# FPGA.net
KiCad netlist of a schematic drawn in Altium Designer
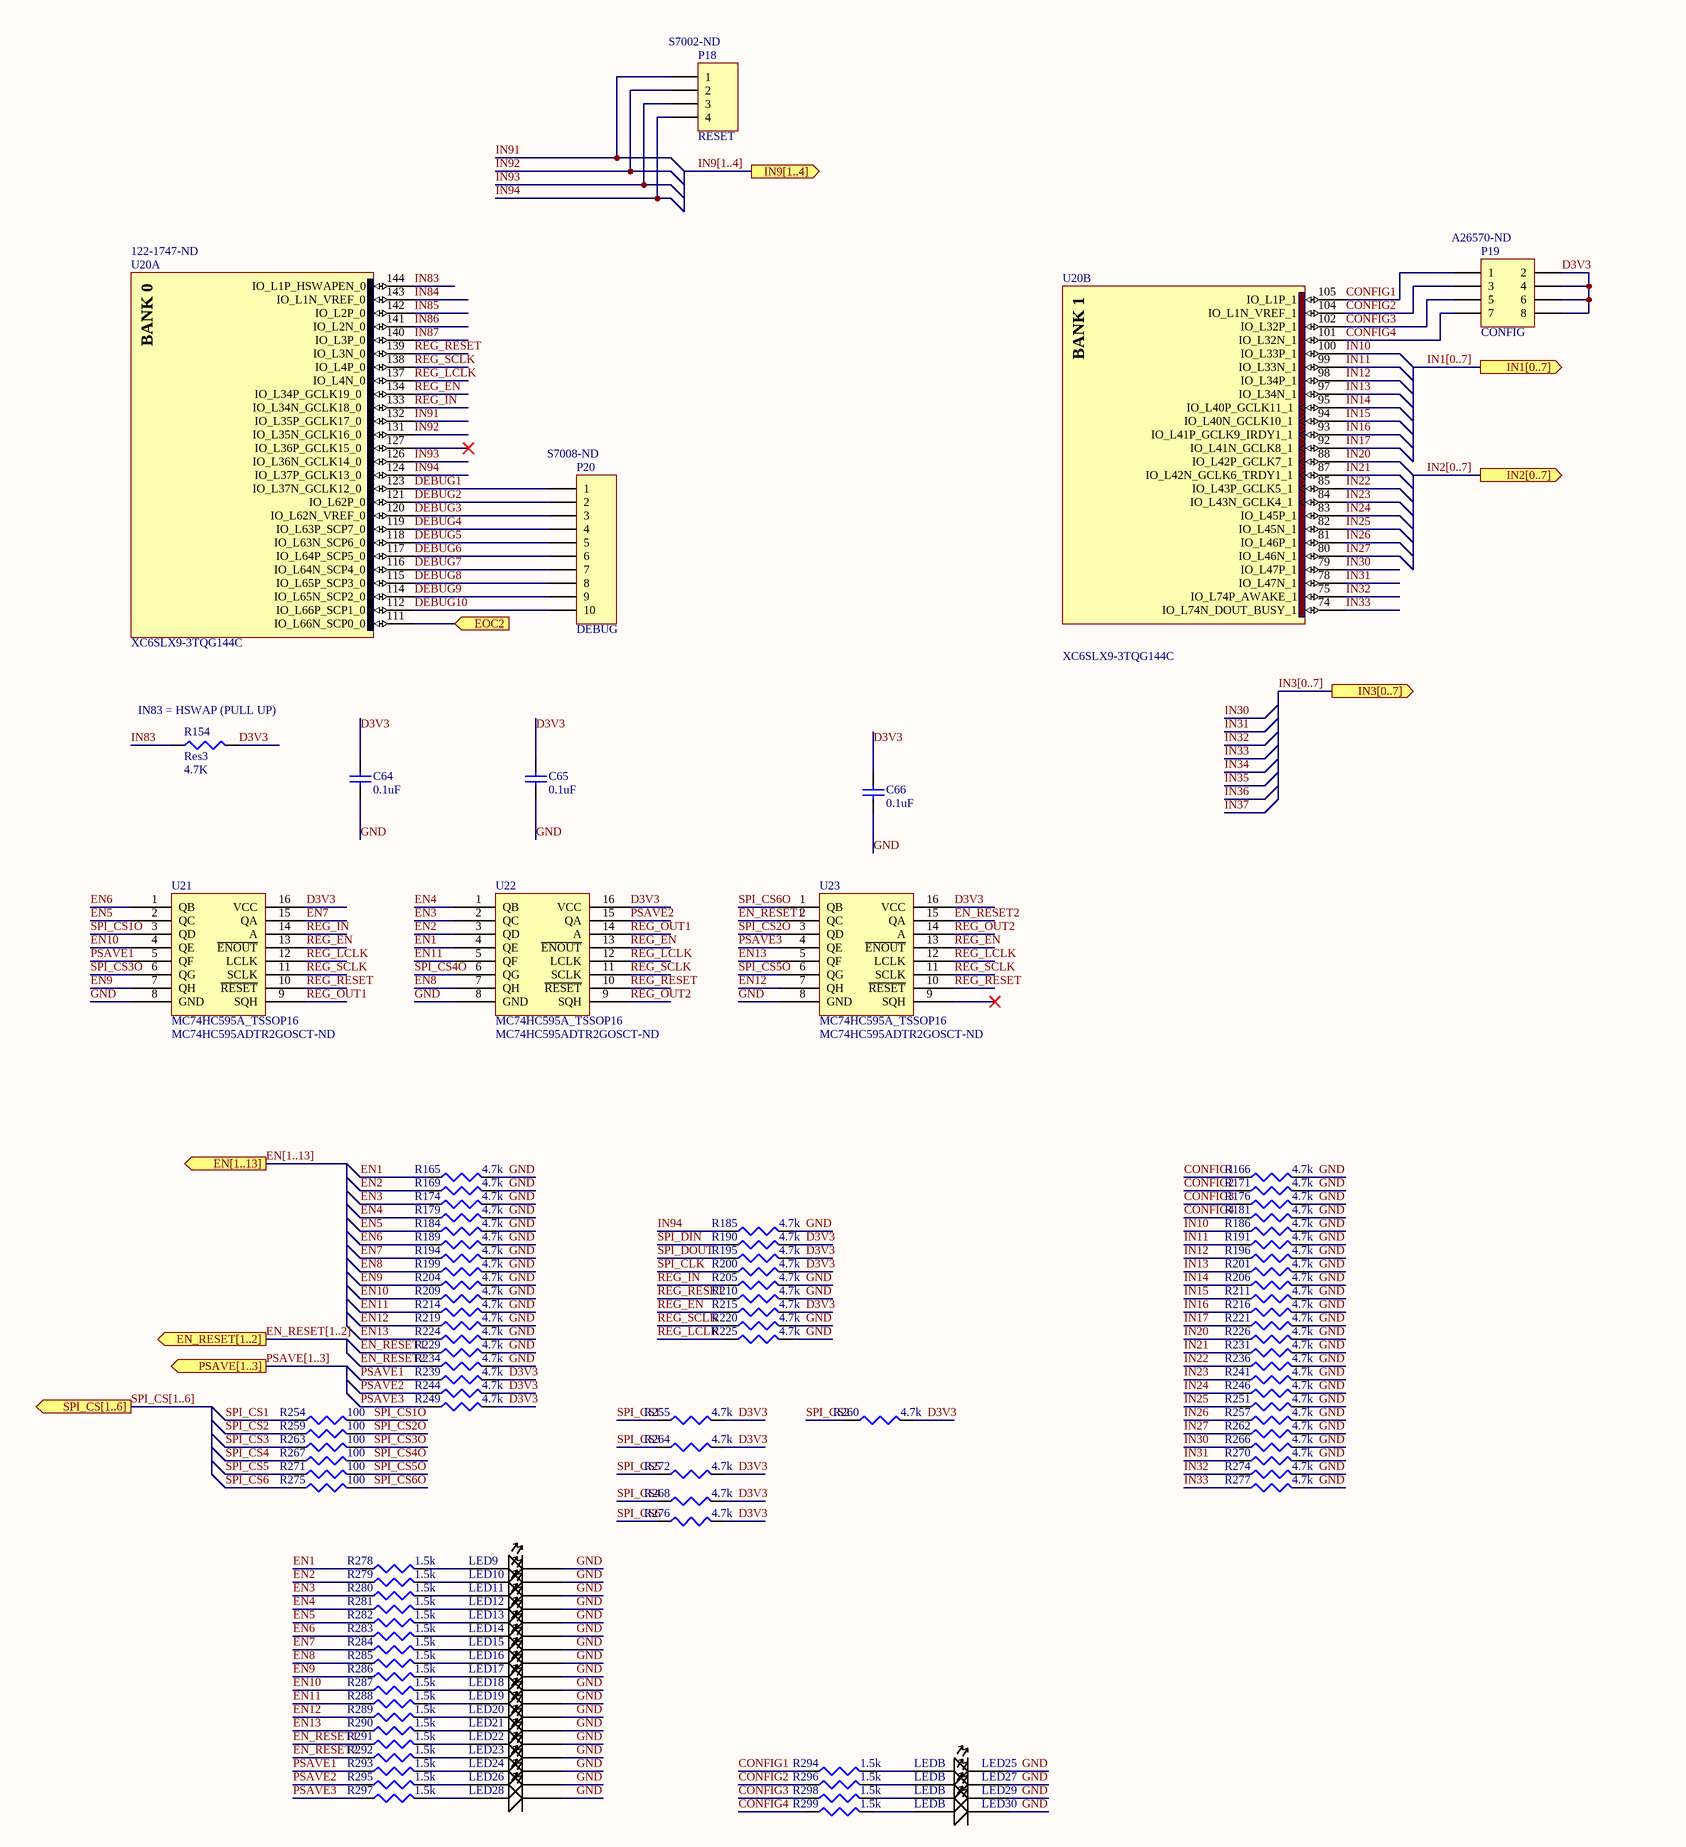
[diagram p0: FPGA.SchDoc, top left]
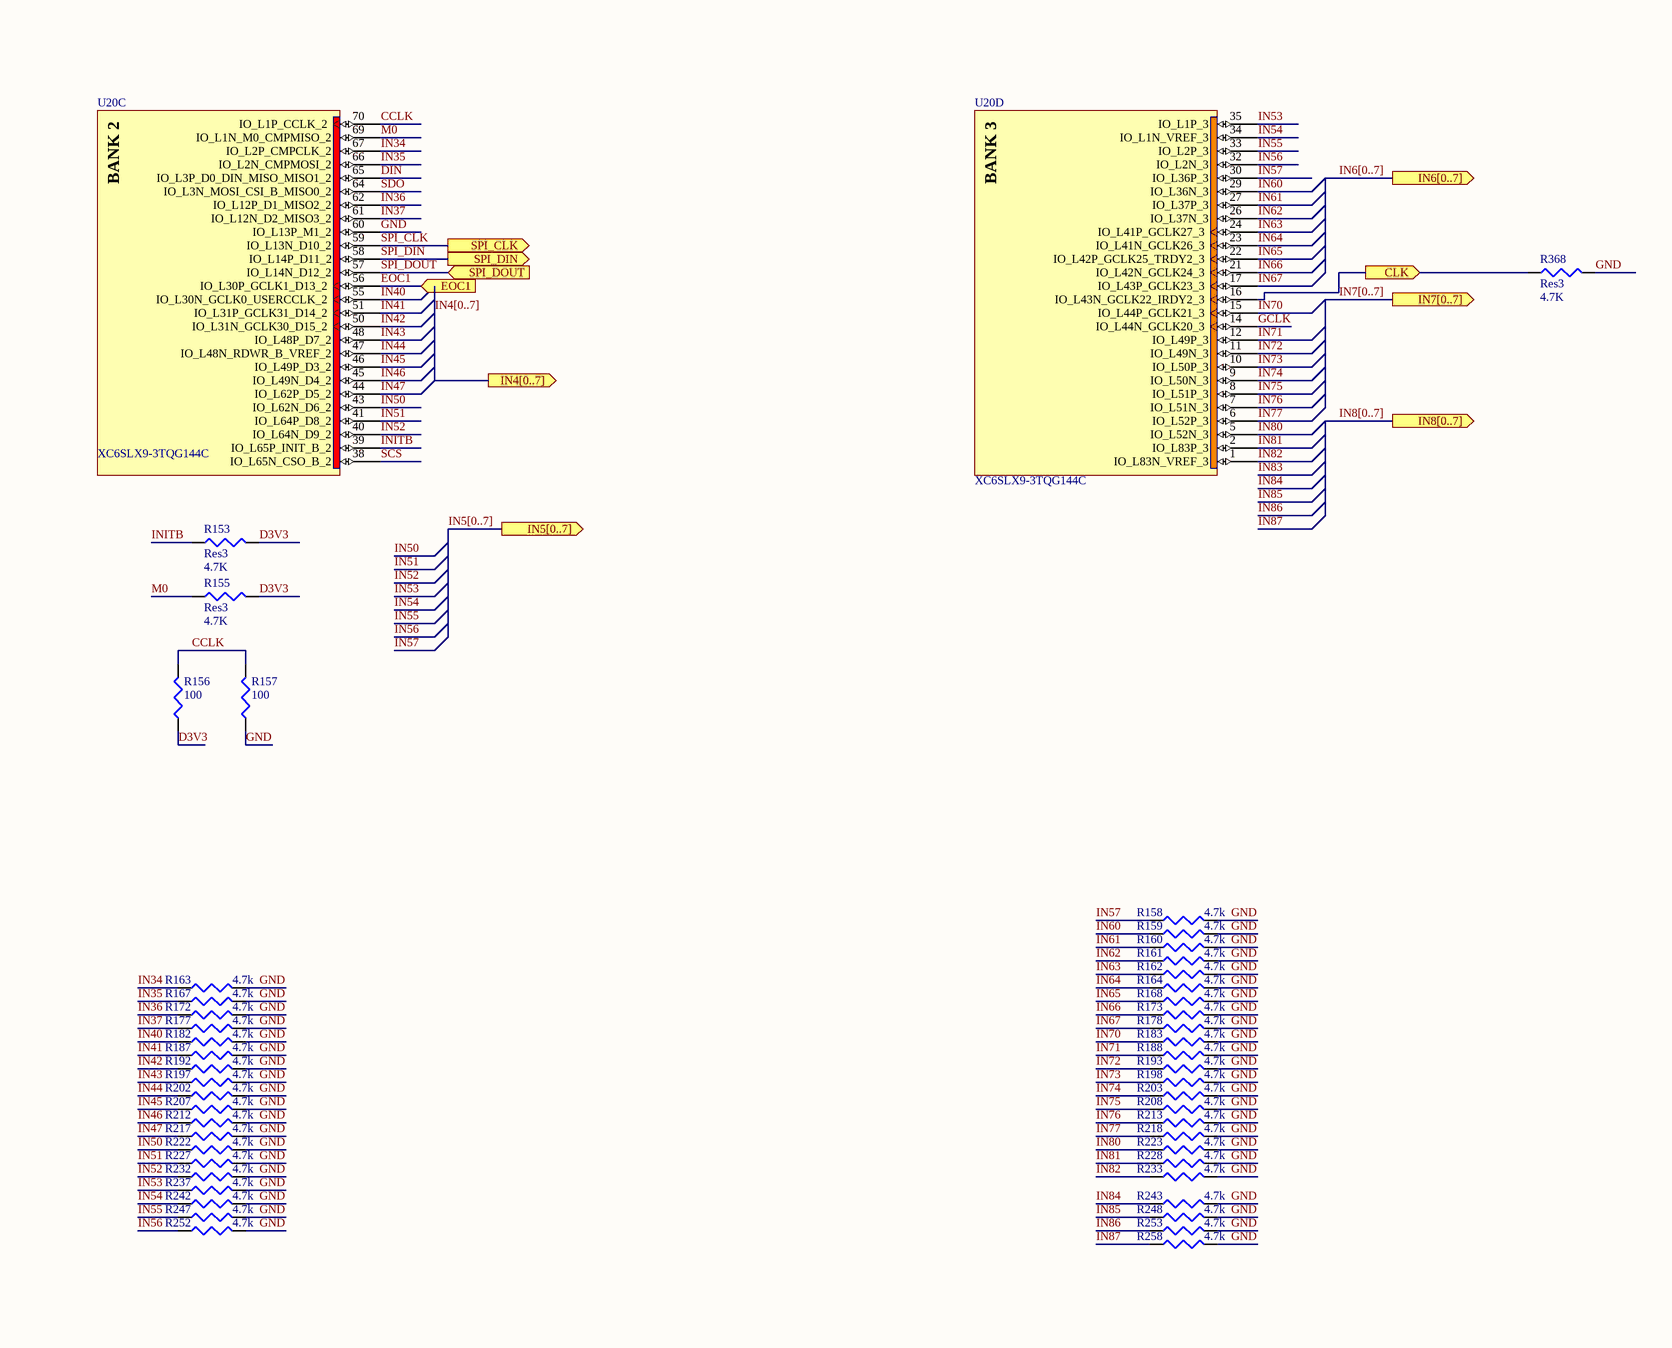
[diagram p1: FPGA.SchDoc, top right]
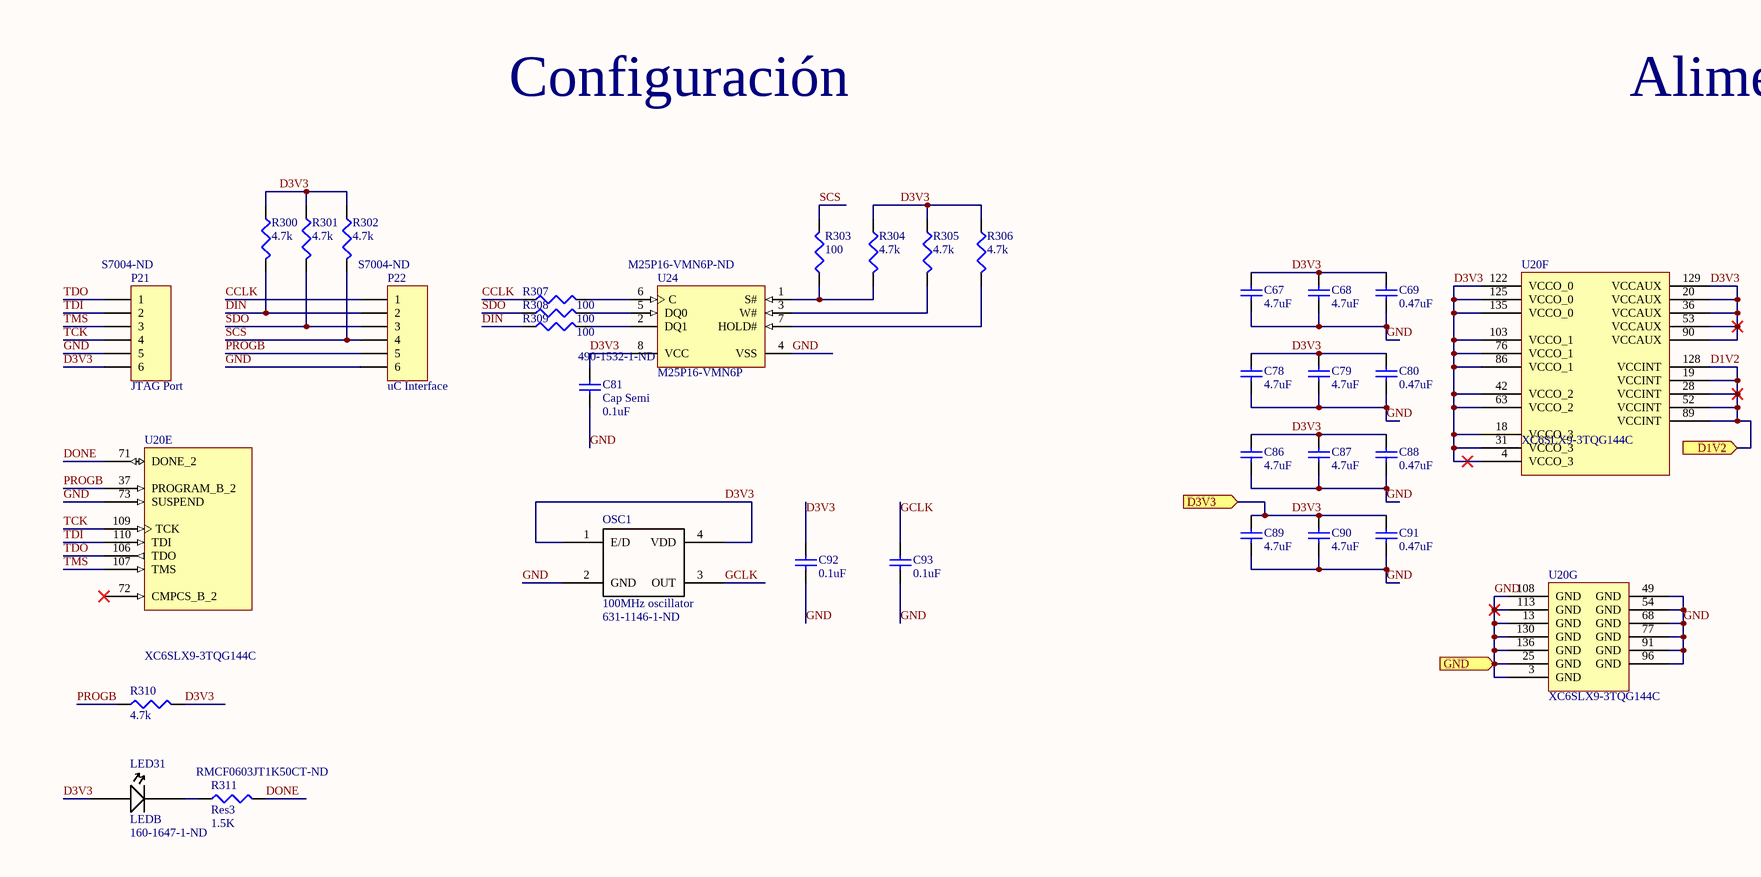
[diagram p2: FPGA.SchDoc, bottom left]
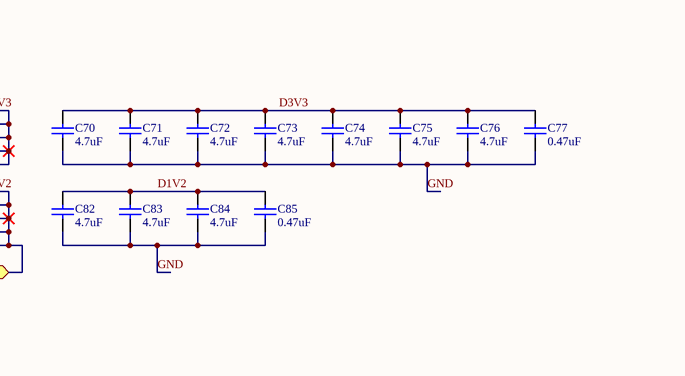
[diagram p3: FPGA.SchDoc, bottom right]

(export (version "E")
  (design (tool "Eeschema 10.0.6"))
  (components
    (comp (ref "C64")
      (value "0.1uF")
      (footprint "J1-0603")
      (description "Capacitor")
      (fields (field (name "Comment") "Cap") (field (name "PUBLISHER") "Altium Limited"))
      (libsource (lib "Miscellaneous Devices") (part "Cap"))
    )
    (comp (ref "C65")
      (value "0.1uF")
      (footprint "J1-0603")
      (description "Capacitor")
      (fields (field (name "Comment") "Cap") (field (name "PUBLISHER") "Altium Limited"))
      (libsource (lib "Miscellaneous Devices") (part "Cap"))
    )
    (comp (ref "C66")
      (value "0.1uF")
      (footprint "J1-0603")
      (description "Capacitor")
      (fields (field (name "Comment") "Cap") (field (name "PUBLISHER") "Altium Limited"))
      (libsource (lib "Miscellaneous Devices") (part "Cap"))
    )
    (comp (ref "C67")
      (value "4.7uF")
      (footprint "J1-0603")
      (description "Capacitor")
      (fields (field (name "Comment") "Cap") (field (name "PUBLISHER") "Altium Limited"))
      (libsource (lib "Miscellaneous Devices") (part "Cap"))
    )
    (comp (ref "C68")
      (value "4.7uF")
      (footprint "J1-0603")
      (description "Capacitor")
      (fields (field (name "Comment") "Cap") (field (name "PUBLISHER") "Altium Limited"))
      (libsource (lib "Miscellaneous Devices") (part "Cap"))
    )
    (comp (ref "C69")
      (value "0.47uF")
      (footprint "J1-0603")
      (description "Capacitor")
      (fields (field (name "Comment") "Cap") (field (name "PUBLISHER") "Altium Limited"))
      (libsource (lib "Miscellaneous Devices") (part "Cap"))
    )
    (comp (ref "C70")
      (value "4.7uF")
      (footprint "J1-0603")
      (description "Capacitor")
      (fields (field (name "Comment") "Cap") (field (name "PUBLISHER") "Altium Limited"))
      (libsource (lib "Miscellaneous Devices") (part "Cap"))
    )
    (comp (ref "C71")
      (value "4.7uF")
      (footprint "J1-0603")
      (description "Capacitor")
      (fields (field (name "Comment") "Cap") (field (name "PUBLISHER") "Altium Limited"))
      (libsource (lib "Miscellaneous Devices") (part "Cap"))
    )
    (comp (ref "C72")
      (value "4.7uF")
      (footprint "J1-0603")
      (description "Capacitor")
      (fields (field (name "Comment") "Cap") (field (name "PUBLISHER") "Altium Limited"))
      (libsource (lib "Miscellaneous Devices") (part "Cap"))
    )
    (comp (ref "C73")
      (value "4.7uF")
      (footprint "J1-0603")
      (description "Capacitor")
      (fields (field (name "Comment") "Cap") (field (name "PUBLISHER") "Altium Limited"))
      (libsource (lib "Miscellaneous Devices") (part "Cap"))
    )
    (comp (ref "C74")
      (value "4.7uF")
      (footprint "J1-0603")
      (description "Capacitor")
      (fields (field (name "Comment") "Cap") (field (name "PUBLISHER") "Altium Limited"))
      (libsource (lib "Miscellaneous Devices") (part "Cap"))
    )
    (comp (ref "C75")
      (value "4.7uF")
      (footprint "J1-0603")
      (description "Capacitor")
      (fields (field (name "Comment") "Cap") (field (name "PUBLISHER") "Altium Limited"))
      (libsource (lib "Miscellaneous Devices") (part "Cap"))
    )
    (comp (ref "C76")
      (value "4.7uF")
      (footprint "J1-0603")
      (description "Capacitor")
      (fields (field (name "Comment") "Cap") (field (name "PUBLISHER") "Altium Limited"))
      (libsource (lib "Miscellaneous Devices") (part "Cap"))
    )
    (comp (ref "C77")
      (value "0.47uF")
      (footprint "J1-0603")
      (description "Capacitor")
      (fields (field (name "Comment") "Cap") (field (name "PUBLISHER") "Altium Limited"))
      (libsource (lib "Miscellaneous Devices") (part "Cap"))
    )
    (comp (ref "C78")
      (value "4.7uF")
      (footprint "J1-0603")
      (description "Capacitor")
      (fields (field (name "Comment") "Cap") (field (name "PUBLISHER") "Altium Limited"))
      (libsource (lib "Miscellaneous Devices") (part "Cap"))
    )
    (comp (ref "C79")
      (value "4.7uF")
      (footprint "J1-0603")
      (description "Capacitor")
      (fields (field (name "Comment") "Cap") (field (name "PUBLISHER") "Altium Limited"))
      (libsource (lib "Miscellaneous Devices") (part "Cap"))
    )
    (comp (ref "C80")
      (value "0.47uF")
      (footprint "J1-0603")
      (description "Capacitor")
      (fields (field (name "Comment") "Cap") (field (name "PUBLISHER") "Altium Limited"))
      (libsource (lib "Miscellaneous Devices") (part "Cap"))
    )
    (comp (ref "C81")
      (value "Cap Semi")
      (footprint "J1-0603")
      (description "Capacitor (Semiconductor SIM Model)")
      (fields
        (field (name "ALTIUM_VALUE") "0.1uF")
        (field (name "SUPPLIER PART NUMBER 1") "490-1532-1-ND")
        (field (name "PUBLISHER") "Altium Limited")
      )
      (libsource (lib "Miscellaneous Devices") (part "Cap Semi"))
    )
    (comp (ref "C82")
      (value "4.7uF")
      (footprint "J1-0603")
      (description "Capacitor")
      (fields (field (name "Comment") "Cap") (field (name "PUBLISHER") "Altium Limited"))
      (libsource (lib "Miscellaneous Devices") (part "Cap"))
    )
    (comp (ref "C83")
      (value "4.7uF")
      (footprint "J1-0603")
      (description "Capacitor")
      (fields (field (name "Comment") "Cap") (field (name "PUBLISHER") "Altium Limited"))
      (libsource (lib "Miscellaneous Devices") (part "Cap"))
    )
    (comp (ref "C84")
      (value "4.7uF")
      (footprint "J1-0603")
      (description "Capacitor")
      (fields (field (name "Comment") "Cap") (field (name "PUBLISHER") "Altium Limited"))
      (libsource (lib "Miscellaneous Devices") (part "Cap"))
    )
    (comp (ref "C85")
      (value "0.47uF")
      (footprint "J1-0603")
      (description "Capacitor")
      (fields (field (name "Comment") "Cap") (field (name "PUBLISHER") "Altium Limited"))
      (libsource (lib "Miscellaneous Devices") (part "Cap"))
    )
    (comp (ref "C86")
      (value "4.7uF")
      (footprint "J1-0603")
      (description "Capacitor")
      (fields (field (name "Comment") "Cap") (field (name "PUBLISHER") "Altium Limited"))
      (libsource (lib "Miscellaneous Devices") (part "Cap"))
    )
    (comp (ref "C87")
      (value "4.7uF")
      (footprint "J1-0603")
      (description "Capacitor")
      (fields (field (name "Comment") "Cap") (field (name "PUBLISHER") "Altium Limited"))
      (libsource (lib "Miscellaneous Devices") (part "Cap"))
    )
    (comp (ref "C88")
      (value "0.47uF")
      (footprint "J1-0603")
      (description "Capacitor")
      (fields (field (name "Comment") "Cap") (field (name "PUBLISHER") "Altium Limited"))
      (libsource (lib "Miscellaneous Devices") (part "Cap"))
    )
    (comp (ref "C89")
      (value "4.7uF")
      (footprint "J1-0603")
      (description "Capacitor")
      (fields (field (name "Comment") "Cap") (field (name "PUBLISHER") "Altium Limited"))
      (libsource (lib "Miscellaneous Devices") (part "Cap"))
    )
    (comp (ref "C90")
      (value "4.7uF")
      (footprint "J1-0603")
      (description "Capacitor")
      (fields (field (name "Comment") "Cap") (field (name "PUBLISHER") "Altium Limited"))
      (libsource (lib "Miscellaneous Devices") (part "Cap"))
    )
    (comp (ref "C91")
      (value "0.47uF")
      (footprint "J1-0603")
      (description "Capacitor")
      (fields (field (name "Comment") "Cap") (field (name "PUBLISHER") "Altium Limited"))
      (libsource (lib "Miscellaneous Devices") (part "Cap"))
    )
    (comp (ref "C92")
      (value "0.1uF")
      (footprint "J1-0603")
      (description "Capacitor")
      (fields (field (name "Comment") "Cap") (field (name "PUBLISHER") "Altium Limited"))
      (libsource (lib "Miscellaneous Devices") (part "Cap"))
    )
    (comp (ref "C93")
      (value "0.1uF")
      (footprint "J1-0603")
      (description "Capacitor")
      (fields (field (name "Comment") "Cap") (field (name "PUBLISHER") "Altium Limited"))
      (libsource (lib "Miscellaneous Devices") (part "Cap"))
    )
    (comp (ref "LED9") (value "LED") (footprint "LED") (libsource (lib "Lib1") (part "LED")))
    (comp (ref "LED10") (value "LED") (footprint "LED") (libsource (lib "Lib1") (part "LED")))
    (comp (ref "LED11") (value "LED") (footprint "LED") (libsource (lib "Lib1") (part "LED")))
    (comp (ref "LED12") (value "LED") (footprint "LED") (libsource (lib "Lib1") (part "LED")))
    (comp (ref "LED13") (value "LED") (footprint "LED") (libsource (lib "Lib1") (part "LED")))
    (comp (ref "LED14") (value "LED") (footprint "LED") (libsource (lib "Lib1") (part "LED")))
    (comp (ref "LED15") (value "LED") (footprint "LED") (libsource (lib "Lib1") (part "LED")))
    (comp (ref "LED16") (value "LED") (footprint "LED") (libsource (lib "Lib1") (part "LED")))
    (comp (ref "LED17") (value "LED") (footprint "LED") (libsource (lib "Lib1") (part "LED")))
    (comp (ref "LED18") (value "LED") (footprint "LED") (libsource (lib "Lib1") (part "LED")))
    (comp (ref "LED19") (value "LED") (footprint "LED") (libsource (lib "Lib1") (part "LED")))
    (comp (ref "LED20") (value "LED") (footprint "LED") (libsource (lib "Lib1") (part "LED")))
    (comp (ref "LED21") (value "LED") (footprint "LED") (libsource (lib "Lib1") (part "LED")))
    (comp (ref "LED22") (value "LED") (footprint "LED") (libsource (lib "Lib1") (part "LED")))
    (comp (ref "LED23") (value "LED") (footprint "LED") (libsource (lib "Lib1") (part "LED")))
    (comp (ref "LED24") (value "LED") (footprint "LED") (libsource (lib "Lib1") (part "LED")))
    (comp (ref "LED25") (value "LEDB") (footprint "LED") (libsource (lib "Lib1") (part "LEDB")))
    (comp (ref "LED26") (value "LED") (footprint "LED") (libsource (lib "Lib1") (part "LED")))
    (comp (ref "LED27") (value "LEDB") (footprint "LED") (libsource (lib "Lib1") (part "LEDB")))
    (comp (ref "LED28") (value "LED") (footprint "LED") (libsource (lib "Lib1") (part "LED")))
    (comp (ref "LED29") (value "LEDB") (footprint "LED") (libsource (lib "Lib1") (part "LEDB")))
    (comp (ref "LED30") (value "LEDB") (footprint "LED") (libsource (lib "Lib1") (part "LEDB")))
    (comp (ref "LED31")
      (value "LEDB")
      (footprint "LED")
      (fields (field (name "SUPPLIER PART NUMBER 1") "160-1647-1-ND"))
      (libsource (lib "Lib1") (part "LEDB"))
    )
    (comp (ref "OSC1")
      (value "100MHz oscillator")
      (footprint "100MHz oscillator")
      (fields (field (name "SUPPLIER PART NUMBER 1") "631-1146-1-ND"))
      (libsource (lib "Lib1") (part "100MHz oscillator"))
    )
    (comp (ref "P18")
      (value "RESET")
      (footprint "HDR1X4")
      (description "Header, 4-Pin")
      (fields (field (name "SUPPLIER PART NUMBER 1") "S7002-ND") (field (name "PUBLISHER") "Altium Limited"))
      (libsource (lib "Miscellaneous Connectors") (part "Header 4"))
    )
    (comp (ref "P19")
      (value "CONFIG")
      (footprint "HDR2X4")
      (description "Header, 4-Pin, Dual row")
      (fields (field (name "SUPPLIER PART NUMBER 1") "A26570-ND") (field (name "PUBLISHER") "Altium Limited"))
      (libsource (lib "Miscellaneous Connectors") (part "Header 4X2"))
    )
    (comp (ref "P20")
      (value "DEBUG")
      (footprint "HDR1X10")
      (description "Header, 10-Pin")
      (fields (field (name "SUPPLIER PART NUMBER 1") "S7008-ND") (field (name "PUBLISHER") "Altium Limited"))
      (libsource (lib "Miscellaneous Connectors") (part "Header 10"))
    )
    (comp (ref "P21")
      (value "JTAG Port")
      (footprint "HDR1X6")
      (description "Header, 6-Pin")
      (fields (field (name "SUPPLIER PART NUMBER 1") "S7004-ND") (field (name "PUBLISHER") "Altium Limited"))
      (libsource (lib "Miscellaneous Connectors") (part "Header 6"))
    )
    (comp (ref "P22")
      (value "uC Interface")
      (footprint "HDR1X6")
      (description "Header, 6-Pin")
      (fields (field (name "SUPPLIER PART NUMBER 1") "S7004-ND") (field (name "PUBLISHER") "Altium Limited"))
      (libsource (lib "Miscellaneous Connectors") (part "Header 6"))
    )
    (comp (ref "R153")
      (value "Res3")
      (footprint "J1-0603")
      (description "Resistor")
      (fields (field (name "ALTIUM_VALUE") "4.7K") (field (name "PUBLISHER") "Altium Limited"))
      (libsource (lib "Miscellaneous Devices") (part "Res3"))
    )
    (comp (ref "R154")
      (value "Res3")
      (footprint "J1-0603")
      (description "Resistor")
      (fields (field (name "ALTIUM_VALUE") "4.7K") (field (name "PUBLISHER") "Altium Limited"))
      (libsource (lib "Miscellaneous Devices") (part "Res3"))
    )
    (comp (ref "R155")
      (value "Res3")
      (footprint "J1-0603")
      (description "Resistor")
      (fields (field (name "ALTIUM_VALUE") "4.7K") (field (name "PUBLISHER") "Altium Limited"))
      (libsource (lib "Miscellaneous Devices") (part "Res3"))
    )
    (comp (ref "R156")
      (value "100")
      (footprint "J1-0603")
      (description "Resistor")
      (fields (field (name "Comment") "Res3") (field (name "PUBLISHER") "Altium Limited"))
      (libsource (lib "Miscellaneous Devices") (part "Res3"))
    )
    (comp (ref "R157")
      (value "100")
      (footprint "J1-0603")
      (description "Resistor")
      (fields (field (name "Comment") "Res3") (field (name "PUBLISHER") "Altium Limited"))
      (libsource (lib "Miscellaneous Devices") (part "Res3"))
    )
    (comp (ref "R158")
      (value "4.7k")
      (footprint "J1-0603")
      (description "Resistor")
      (fields (field (name "Comment") "Res3") (field (name "PUBLISHER") "Altium Limited"))
      (libsource (lib "Miscellaneous Devices") (part "Res3"))
    )
    (comp (ref "R159")
      (value "4.7k")
      (footprint "J1-0603")
      (description "Resistor")
      (fields (field (name "Comment") "Res3") (field (name "PUBLISHER") "Altium Limited"))
      (libsource (lib "Miscellaneous Devices") (part "Res3"))
    )
    (comp (ref "R160")
      (value "4.7k")
      (footprint "J1-0603")
      (description "Resistor")
      (fields (field (name "Comment") "Res3") (field (name "PUBLISHER") "Altium Limited"))
      (libsource (lib "Miscellaneous Devices") (part "Res3"))
    )
    (comp (ref "R161")
      (value "4.7k")
      (footprint "J1-0603")
      (description "Resistor")
      (fields (field (name "Comment") "Res3") (field (name "PUBLISHER") "Altium Limited"))
      (libsource (lib "Miscellaneous Devices") (part "Res3"))
    )
    (comp (ref "R162")
      (value "4.7k")
      (footprint "J1-0603")
      (description "Resistor")
      (fields (field (name "Comment") "Res3") (field (name "PUBLISHER") "Altium Limited"))
      (libsource (lib "Miscellaneous Devices") (part "Res3"))
    )
    (comp (ref "R163")
      (value "4.7k")
      (footprint "J1-0603")
      (description "Resistor")
      (fields (field (name "Comment") "Res3") (field (name "PUBLISHER") "Altium Limited"))
      (libsource (lib "Miscellaneous Devices") (part "Res3"))
    )
    (comp (ref "R164")
      (value "4.7k")
      (footprint "J1-0603")
      (description "Resistor")
      (fields (field (name "Comment") "Res3") (field (name "PUBLISHER") "Altium Limited"))
      (libsource (lib "Miscellaneous Devices") (part "Res3"))
    )
    (comp (ref "R165")
      (value "4.7k")
      (footprint "J1-0603")
      (description "Resistor")
      (fields (field (name "Comment") "Res3") (field (name "PUBLISHER") "Altium Limited"))
      (libsource (lib "Miscellaneous Devices") (part "Res3"))
    )
    (comp (ref "R166")
      (value "4.7k")
      (footprint "J1-0603")
      (description "Resistor")
      (fields (field (name "Comment") "Res3") (field (name "PUBLISHER") "Altium Limited"))
      (libsource (lib "Miscellaneous Devices") (part "Res3"))
    )
    (comp (ref "R167")
      (value "4.7k")
      (footprint "J1-0603")
      (description "Resistor")
      (fields (field (name "Comment") "Res3") (field (name "PUBLISHER") "Altium Limited"))
      (libsource (lib "Miscellaneous Devices") (part "Res3"))
    )
    (comp (ref "R168")
      (value "4.7k")
      (footprint "J1-0603")
      (description "Resistor")
      (fields (field (name "Comment") "Res3") (field (name "PUBLISHER") "Altium Limited"))
      (libsource (lib "Miscellaneous Devices") (part "Res3"))
    )
    (comp (ref "R169")
      (value "4.7k")
      (footprint "J1-0603")
      (description "Resistor")
      (fields (field (name "Comment") "Res3") (field (name "PUBLISHER") "Altium Limited"))
      (libsource (lib "Miscellaneous Devices") (part "Res3"))
    )
    (comp (ref "R171")
      (value "4.7k")
      (footprint "J1-0603")
      (description "Resistor")
      (fields (field (name "Comment") "Res3") (field (name "PUBLISHER") "Altium Limited"))
      (libsource (lib "Miscellaneous Devices") (part "Res3"))
    )
    (comp (ref "R172")
      (value "4.7k")
      (footprint "J1-0603")
      (description "Resistor")
      (fields (field (name "Comment") "Res3") (field (name "PUBLISHER") "Altium Limited"))
      (libsource (lib "Miscellaneous Devices") (part "Res3"))
    )
    (comp (ref "R173")
      (value "4.7k")
      (footprint "J1-0603")
      (description "Resistor")
      (fields (field (name "Comment") "Res3") (field (name "PUBLISHER") "Altium Limited"))
      (libsource (lib "Miscellaneous Devices") (part "Res3"))
    )
    (comp (ref "R174")
      (value "4.7k")
      (footprint "J1-0603")
      (description "Resistor")
      (fields (field (name "Comment") "Res3") (field (name "PUBLISHER") "Altium Limited"))
      (libsource (lib "Miscellaneous Devices") (part "Res3"))
    )
    (comp (ref "R176")
      (value "4.7k")
      (footprint "J1-0603")
      (description "Resistor")
      (fields (field (name "Comment") "Res3") (field (name "PUBLISHER") "Altium Limited"))
      (libsource (lib "Miscellaneous Devices") (part "Res3"))
    )
    (comp (ref "R177")
      (value "4.7k")
      (footprint "J1-0603")
      (description "Resistor")
      (fields (field (name "Comment") "Res3") (field (name "PUBLISHER") "Altium Limited"))
      (libsource (lib "Miscellaneous Devices") (part "Res3"))
    )
    (comp (ref "R178")
      (value "4.7k")
      (footprint "J1-0603")
      (description "Resistor")
      (fields (field (name "Comment") "Res3") (field (name "PUBLISHER") "Altium Limited"))
      (libsource (lib "Miscellaneous Devices") (part "Res3"))
    )
    (comp (ref "R179")
      (value "4.7k")
      (footprint "J1-0603")
      (description "Resistor")
      (fields (field (name "Comment") "Res3") (field (name "PUBLISHER") "Altium Limited"))
      (libsource (lib "Miscellaneous Devices") (part "Res3"))
    )
    (comp (ref "R181")
      (value "4.7k")
      (footprint "J1-0603")
      (description "Resistor")
      (fields (field (name "Comment") "Res3") (field (name "PUBLISHER") "Altium Limited"))
      (libsource (lib "Miscellaneous Devices") (part "Res3"))
    )
    (comp (ref "R182")
      (value "4.7k")
      (footprint "J1-0603")
      (description "Resistor")
      (fields (field (name "Comment") "Res3") (field (name "PUBLISHER") "Altium Limited"))
      (libsource (lib "Miscellaneous Devices") (part "Res3"))
    )
    (comp (ref "R183")
      (value "4.7k")
      (footprint "J1-0603")
      (description "Resistor")
      (fields (field (name "Comment") "Res3") (field (name "PUBLISHER") "Altium Limited"))
      (libsource (lib "Miscellaneous Devices") (part "Res3"))
    )
    (comp (ref "R184")
      (value "4.7k")
      (footprint "J1-0603")
      (description "Resistor")
      (fields (field (name "Comment") "Res3") (field (name "PUBLISHER") "Altium Limited"))
      (libsource (lib "Miscellaneous Devices") (part "Res3"))
    )
    (comp (ref "R185")
      (value "4.7k")
      (footprint "J1-0603")
      (description "Resistor")
      (fields (field (name "Comment") "Res3") (field (name "PUBLISHER") "Altium Limited"))
      (libsource (lib "Miscellaneous Devices") (part "Res3"))
    )
    (comp (ref "R186")
      (value "4.7k")
      (footprint "J1-0603")
      (description "Resistor")
      (fields (field (name "Comment") "Res3") (field (name "PUBLISHER") "Altium Limited"))
      (libsource (lib "Miscellaneous Devices") (part "Res3"))
    )
    (comp (ref "R187")
      (value "4.7k")
      (footprint "J1-0603")
      (description "Resistor")
      (fields (field (name "Comment") "Res3") (field (name "PUBLISHER") "Altium Limited"))
      (libsource (lib "Miscellaneous Devices") (part "Res3"))
    )
    (comp (ref "R188")
      (value "4.7k")
      (footprint "J1-0603")
      (description "Resistor")
      (fields (field (name "Comment") "Res3") (field (name "PUBLISHER") "Altium Limited"))
      (libsource (lib "Miscellaneous Devices") (part "Res3"))
    )
    (comp (ref "R189")
      (value "4.7k")
      (footprint "J1-0603")
      (description "Resistor")
      (fields (field (name "Comment") "Res3") (field (name "PUBLISHER") "Altium Limited"))
      (libsource (lib "Miscellaneous Devices") (part "Res3"))
    )
    (comp (ref "R190")
      (value "4.7k")
      (footprint "J1-0603")
      (description "Resistor")
      (fields (field (name "Comment") "Res3") (field (name "PUBLISHER") "Altium Limited"))
      (libsource (lib "Miscellaneous Devices") (part "Res3"))
    )
    (comp (ref "R191")
      (value "4.7k")
      (footprint "J1-0603")
      (description "Resistor")
      (fields (field (name "Comment") "Res3") (field (name "PUBLISHER") "Altium Limited"))
      (libsource (lib "Miscellaneous Devices") (part "Res3"))
    )
    (comp (ref "R192")
      (value "4.7k")
      (footprint "J1-0603")
      (description "Resistor")
      (fields (field (name "Comment") "Res3") (field (name "PUBLISHER") "Altium Limited"))
      (libsource (lib "Miscellaneous Devices") (part "Res3"))
    )
    (comp (ref "R193")
      (value "4.7k")
      (footprint "J1-0603")
      (description "Resistor")
      (fields (field (name "Comment") "Res3") (field (name "PUBLISHER") "Altium Limited"))
      (libsource (lib "Miscellaneous Devices") (part "Res3"))
    )
    (comp (ref "R194")
      (value "4.7k")
      (footprint "J1-0603")
      (description "Resistor")
      (fields (field (name "Comment") "Res3") (field (name "PUBLISHER") "Altium Limited"))
      (libsource (lib "Miscellaneous Devices") (part "Res3"))
    )
    (comp (ref "R195")
      (value "4.7k")
      (footprint "J1-0603")
      (description "Resistor")
      (fields (field (name "Comment") "Res3") (field (name "PUBLISHER") "Altium Limited"))
      (libsource (lib "Miscellaneous Devices") (part "Res3"))
    )
    (comp (ref "R196")
      (value "4.7k")
      (footprint "J1-0603")
      (description "Resistor")
      (fields (field (name "Comment") "Res3") (field (name "PUBLISHER") "Altium Limited"))
      (libsource (lib "Miscellaneous Devices") (part "Res3"))
    )
    (comp (ref "R197")
      (value "4.7k")
      (footprint "J1-0603")
      (description "Resistor")
      (fields (field (name "Comment") "Res3") (field (name "PUBLISHER") "Altium Limited"))
      (libsource (lib "Miscellaneous Devices") (part "Res3"))
    )
    (comp (ref "R198")
      (value "4.7k")
      (footprint "J1-0603")
      (description "Resistor")
      (fields (field (name "Comment") "Res3") (field (name "PUBLISHER") "Altium Limited"))
      (libsource (lib "Miscellaneous Devices") (part "Res3"))
    )
    (comp (ref "R199")
      (value "4.7k")
      (footprint "J1-0603")
      (description "Resistor")
      (fields (field (name "Comment") "Res3") (field (name "PUBLISHER") "Altium Limited"))
      (libsource (lib "Miscellaneous Devices") (part "Res3"))
    )
    (comp (ref "R200")
      (value "4.7k")
      (footprint "J1-0603")
      (description "Resistor")
      (fields (field (name "Comment") "Res3") (field (name "PUBLISHER") "Altium Limited"))
      (libsource (lib "Miscellaneous Devices") (part "Res3"))
    )
    (comp (ref "R201")
      (value "4.7k")
      (footprint "J1-0603")
      (description "Resistor")
      (fields (field (name "Comment") "Res3") (field (name "PUBLISHER") "Altium Limited"))
      (libsource (lib "Miscellaneous Devices") (part "Res3"))
    )
    (comp (ref "R202")
      (value "4.7k")
      (footprint "J1-0603")
      (description "Resistor")
      (fields (field (name "Comment") "Res3") (field (name "PUBLISHER") "Altium Limited"))
      (libsource (lib "Miscellaneous Devices") (part "Res3"))
    )
    (comp (ref "R203")
      (value "4.7k")
      (footprint "J1-0603")
      (description "Resistor")
      (fields (field (name "Comment") "Res3") (field (name "PUBLISHER") "Altium Limited"))
      (libsource (lib "Miscellaneous Devices") (part "Res3"))
    )
    (comp (ref "R204")
      (value "4.7k")
      (footprint "J1-0603")
      (description "Resistor")
      (fields (field (name "Comment") "Res3") (field (name "PUBLISHER") "Altium Limited"))
      (libsource (lib "Miscellaneous Devices") (part "Res3"))
    )
    (comp (ref "R205")
      (value "4.7k")
      (footprint "J1-0603")
      (description "Resistor")
      (fields (field (name "Comment") "Res3") (field (name "PUBLISHER") "Altium Limited"))
      (libsource (lib "Miscellaneous Devices") (part "Res3"))
    )
    (comp (ref "R206")
      (value "4.7k")
      (footprint "J1-0603")
      (description "Resistor")
      (fields (field (name "Comment") "Res3") (field (name "PUBLISHER") "Altium Limited"))
      (libsource (lib "Miscellaneous Devices") (part "Res3"))
    )
    (comp (ref "R207")
      (value "4.7k")
      (footprint "J1-0603")
      (description "Resistor")
      (fields (field (name "Comment") "Res3") (field (name "PUBLISHER") "Altium Limited"))
      (libsource (lib "Miscellaneous Devices") (part "Res3"))
    )
    (comp (ref "R208")
      (value "4.7k")
      (footprint "J1-0603")
      (description "Resistor")
      (fields (field (name "Comment") "Res3") (field (name "PUBLISHER") "Altium Limited"))
      (libsource (lib "Miscellaneous Devices") (part "Res3"))
    )
    (comp (ref "R209")
      (value "4.7k")
      (footprint "J1-0603")
      (description "Resistor")
      (fields (field (name "Comment") "Res3") (field (name "PUBLISHER") "Altium Limited"))
      (libsource (lib "Miscellaneous Devices") (part "Res3"))
    )
    (comp (ref "R210")
      (value "4.7k")
      (footprint "J1-0603")
      (description "Resistor")
      (fields (field (name "Comment") "Res3") (field (name "PUBLISHER") "Altium Limited"))
      (libsource (lib "Miscellaneous Devices") (part "Res3"))
    )
    (comp (ref "R211")
      (value "4.7k")
      (footprint "J1-0603")
      (description "Resistor")
      (fields (field (name "Comment") "Res3") (field (name "PUBLISHER") "Altium Limited"))
      (libsource (lib "Miscellaneous Devices") (part "Res3"))
    )
    (comp (ref "R212")
      (value "4.7k")
      (footprint "J1-0603")
      (description "Resistor")
      (fields (field (name "Comment") "Res3") (field (name "PUBLISHER") "Altium Limited"))
      (libsource (lib "Miscellaneous Devices") (part "Res3"))
    )
    (comp (ref "R213")
      (value "4.7k")
      (footprint "J1-0603")
      (description "Resistor")
      (fields (field (name "Comment") "Res3") (field (name "PUBLISHER") "Altium Limited"))
      (libsource (lib "Miscellaneous Devices") (part "Res3"))
    )
    (comp (ref "R214")
      (value "4.7k")
      (footprint "J1-0603")
      (description "Resistor")
      (fields (field (name "Comment") "Res3") (field (name "PUBLISHER") "Altium Limited"))
      (libsource (lib "Miscellaneous Devices") (part "Res3"))
    )
    (comp (ref "R215")
      (value "4.7k")
      (footprint "J1-0603")
      (description "Resistor")
      (fields (field (name "Comment") "Res3") (field (name "PUBLISHER") "Altium Limited"))
      (libsource (lib "Miscellaneous Devices") (part "Res3"))
    )
    (comp (ref "R216")
      (value "4.7k")
      (footprint "J1-0603")
      (description "Resistor")
      (fields (field (name "Comment") "Res3") (field (name "PUBLISHER") "Altium Limited"))
      (libsource (lib "Miscellaneous Devices") (part "Res3"))
    )
    (comp (ref "R217")
      (value "4.7k")
      (footprint "J1-0603")
      (description "Resistor")
      (fields (field (name "Comment") "Res3") (field (name "PUBLISHER") "Altium Limited"))
      (libsource (lib "Miscellaneous Devices") (part "Res3"))
    )
    (comp (ref "R218")
      (value "4.7k")
      (footprint "J1-0603")
      (description "Resistor")
      (fields (field (name "Comment") "Res3") (field (name "PUBLISHER") "Altium Limited"))
      (libsource (lib "Miscellaneous Devices") (part "Res3"))
    )
    (comp (ref "R219")
      (value "4.7k")
      (footprint "J1-0603")
      (description "Resistor")
      (fields (field (name "Comment") "Res3") (field (name "PUBLISHER") "Altium Limited"))
      (libsource (lib "Miscellaneous Devices") (part "Res3"))
    )
    (comp (ref "R220")
      (value "4.7k")
      (footprint "J1-0603")
      (description "Resistor")
      (fields (field (name "Comment") "Res3") (field (name "PUBLISHER") "Altium Limited"))
      (libsource (lib "Miscellaneous Devices") (part "Res3"))
    )
    (comp (ref "R221")
      (value "4.7k")
      (footprint "J1-0603")
      (description "Resistor")
      (fields (field (name "Comment") "Res3") (field (name "PUBLISHER") "Altium Limited"))
      (libsource (lib "Miscellaneous Devices") (part "Res3"))
    )
    (comp (ref "R222")
      (value "4.7k")
      (footprint "J1-0603")
      (description "Resistor")
      (fields (field (name "Comment") "Res3") (field (name "PUBLISHER") "Altium Limited"))
      (libsource (lib "Miscellaneous Devices") (part "Res3"))
    )
    (comp (ref "R223")
      (value "4.7k")
      (footprint "J1-0603")
      (description "Resistor")
      (fields (field (name "Comment") "Res3") (field (name "PUBLISHER") "Altium Limited"))
      (libsource (lib "Miscellaneous Devices") (part "Res3"))
    )
    (comp (ref "R224")
      (value "4.7k")
      (footprint "J1-0603")
      (description "Resistor")
      (fields (field (name "Comment") "Res3") (field (name "PUBLISHER") "Altium Limited"))
      (libsource (lib "Miscellaneous Devices") (part "Res3"))
    )
    (comp (ref "R225")
      (value "4.7k")
      (footprint "J1-0603")
      (description "Resistor")
      (fields (field (name "Comment") "Res3") (field (name "PUBLISHER") "Altium Limited"))
      (libsource (lib "Miscellaneous Devices") (part "Res3"))
    )
    (comp (ref "R226")
      (value "4.7k")
      (footprint "J1-0603")
      (description "Resistor")
      (fields (field (name "Comment") "Res3") (field (name "PUBLISHER") "Altium Limited"))
      (libsource (lib "Miscellaneous Devices") (part "Res3"))
    )
    (comp (ref "R227")
      (value "4.7k")
      (footprint "J1-0603")
      (description "Resistor")
      (fields (field (name "Comment") "Res3") (field (name "PUBLISHER") "Altium Limited"))
      (libsource (lib "Miscellaneous Devices") (part "Res3"))
    )
    (comp (ref "R228")
      (value "4.7k")
      (footprint "J1-0603")
      (description "Resistor")
      (fields (field (name "Comment") "Res3") (field (name "PUBLISHER") "Altium Limited"))
      (libsource (lib "Miscellaneous Devices") (part "Res3"))
    )
    (comp (ref "R229")
      (value "4.7k")
      (footprint "J1-0603")
      (description "Resistor")
      (fields (field (name "Comment") "Res3") (field (name "PUBLISHER") "Altium Limited"))
      (libsource (lib "Miscellaneous Devices") (part "Res3"))
    )
    (comp (ref "R231")
      (value "4.7k")
      (footprint "J1-0603")
      (description "Resistor")
      (fields (field (name "Comment") "Res3") (field (name "PUBLISHER") "Altium Limited"))
      (libsource (lib "Miscellaneous Devices") (part "Res3"))
    )
    (comp (ref "R232")
      (value "4.7k")
      (footprint "J1-0603")
      (description "Resistor")
      (fields (field (name "Comment") "Res3") (field (name "PUBLISHER") "Altium Limited"))
      (libsource (lib "Miscellaneous Devices") (part "Res3"))
    )
    (comp (ref "R233")
      (value "4.7k")
      (footprint "J1-0603")
      (description "Resistor")
      (fields (field (name "Comment") "Res3") (field (name "PUBLISHER") "Altium Limited"))
      (libsource (lib "Miscellaneous Devices") (part "Res3"))
    )
    (comp (ref "R234")
      (value "4.7k")
      (footprint "J1-0603")
      (description "Resistor")
      (fields (field (name "Comment") "Res3") (field (name "PUBLISHER") "Altium Limited"))
      (libsource (lib "Miscellaneous Devices") (part "Res3"))
    )
    (comp (ref "R236")
      (value "4.7k")
      (footprint "J1-0603")
      (description "Resistor")
      (fields (field (name "Comment") "Res3") (field (name "PUBLISHER") "Altium Limited"))
      (libsource (lib "Miscellaneous Devices") (part "Res3"))
    )
    (comp (ref "R237")
      (value "4.7k")
      (footprint "J1-0603")
      (description "Resistor")
      (fields (field (name "Comment") "Res3") (field (name "PUBLISHER") "Altium Limited"))
      (libsource (lib "Miscellaneous Devices") (part "Res3"))
    )
    (comp (ref "R239")
      (value "4.7k")
      (footprint "J1-0603")
      (description "Resistor")
      (fields (field (name "Comment") "Res3") (field (name "PUBLISHER") "Altium Limited"))
      (libsource (lib "Miscellaneous Devices") (part "Res3"))
    )
    (comp (ref "R241")
      (value "4.7k")
      (footprint "J1-0603")
      (description "Resistor")
      (fields (field (name "Comment") "Res3") (field (name "PUBLISHER") "Altium Limited"))
      (libsource (lib "Miscellaneous Devices") (part "Res3"))
    )
    (comp (ref "R242")
      (value "4.7k")
      (footprint "J1-0603")
      (description "Resistor")
      (fields (field (name "Comment") "Res3") (field (name "PUBLISHER") "Altium Limited"))
      (libsource (lib "Miscellaneous Devices") (part "Res3"))
    )
    (comp (ref "R243")
      (value "4.7k")
      (footprint "J1-0603")
      (description "Resistor")
      (fields (field (name "Comment") "Res3") (field (name "PUBLISHER") "Altium Limited"))
      (libsource (lib "Miscellaneous Devices") (part "Res3"))
    )
    (comp (ref "R244")
      (value "4.7k")
      (footprint "J1-0603")
      (description "Resistor")
      (fields (field (name "Comment") "Res3") (field (name "PUBLISHER") "Altium Limited"))
      (libsource (lib "Miscellaneous Devices") (part "Res3"))
    )
    (comp (ref "R246")
      (value "4.7k")
      (footprint "J1-0603")
      (description "Resistor")
      (fields (field (name "Comment") "Res3") (field (name "PUBLISHER") "Altium Limited"))
      (libsource (lib "Miscellaneous Devices") (part "Res3"))
    )
    (comp (ref "R247")
      (value "4.7k")
      (footprint "J1-0603")
      (description "Resistor")
      (fields (field (name "Comment") "Res3") (field (name "PUBLISHER") "Altium Limited"))
      (libsource (lib "Miscellaneous Devices") (part "Res3"))
    )
    (comp (ref "R248")
      (value "4.7k")
      (footprint "J1-0603")
      (description "Resistor")
      (fields (field (name "Comment") "Res3") (field (name "PUBLISHER") "Altium Limited"))
      (libsource (lib "Miscellaneous Devices") (part "Res3"))
    )
    (comp (ref "R249")
      (value "4.7k")
      (footprint "J1-0603")
      (description "Resistor")
      (fields (field (name "Comment") "Res3") (field (name "PUBLISHER") "Altium Limited"))
      (libsource (lib "Miscellaneous Devices") (part "Res3"))
    )
    (comp (ref "R251")
      (value "4.7k")
      (footprint "J1-0603")
      (description "Resistor")
      (fields (field (name "Comment") "Res3") (field (name "PUBLISHER") "Altium Limited"))
      (libsource (lib "Miscellaneous Devices") (part "Res3"))
    )
    (comp (ref "R252")
      (value "4.7k")
      (footprint "J1-0603")
      (description "Resistor")
      (fields (field (name "Comment") "Res3") (field (name "PUBLISHER") "Altium Limited"))
      (libsource (lib "Miscellaneous Devices") (part "Res3"))
    )
    (comp (ref "R253")
      (value "4.7k")
      (footprint "J1-0603")
      (description "Resistor")
      (fields (field (name "Comment") "Res3") (field (name "PUBLISHER") "Altium Limited"))
      (libsource (lib "Miscellaneous Devices") (part "Res3"))
    )
    (comp (ref "R254")
      (value "100")
      (footprint "J1-0603")
      (description "Resistor")
      (fields (field (name "Comment") "Res3") (field (name "PUBLISHER") "Altium Limited"))
      (libsource (lib "Miscellaneous Devices") (part "Res3"))
    )
    (comp (ref "R255")
      (value "4.7k")
      (footprint "J1-0603")
      (description "Resistor")
      (fields (field (name "Comment") "Res3") (field (name "PUBLISHER") "Altium Limited"))
      (libsource (lib "Miscellaneous Devices") (part "Res3"))
    )
    (comp (ref "R257")
      (value "4.7k")
      (footprint "J1-0603")
      (description "Resistor")
      (fields (field (name "Comment") "Res3") (field (name "PUBLISHER") "Altium Limited"))
      (libsource (lib "Miscellaneous Devices") (part "Res3"))
    )
    (comp (ref "R258")
      (value "4.7k")
      (footprint "J1-0603")
      (description "Resistor")
      (fields (field (name "Comment") "Res3") (field (name "PUBLISHER") "Altium Limited"))
      (libsource (lib "Miscellaneous Devices") (part "Res3"))
    )
    (comp (ref "R259")
      (value "100")
      (footprint "J1-0603")
      (description "Resistor")
      (fields (field (name "Comment") "Res3") (field (name "PUBLISHER") "Altium Limited"))
      (libsource (lib "Miscellaneous Devices") (part "Res3"))
    )
    (comp (ref "R260")
      (value "4.7k")
      (footprint "J1-0603")
      (description "Resistor")
      (fields (field (name "Comment") "Res3") (field (name "PUBLISHER") "Altium Limited"))
      (libsource (lib "Miscellaneous Devices") (part "Res3"))
    )
    (comp (ref "R262")
      (value "4.7k")
      (footprint "J1-0603")
      (description "Resistor")
      (fields (field (name "Comment") "Res3") (field (name "PUBLISHER") "Altium Limited"))
      (libsource (lib "Miscellaneous Devices") (part "Res3"))
    )
    (comp (ref "R263")
      (value "100")
      (footprint "J1-0603")
      (description "Resistor")
      (fields (field (name "Comment") "Res3") (field (name "PUBLISHER") "Altium Limited"))
      (libsource (lib "Miscellaneous Devices") (part "Res3"))
    )
    (comp (ref "R264")
      (value "4.7k")
      (footprint "J1-0603")
      (description "Resistor")
      (fields (field (name "Comment") "Res3") (field (name "PUBLISHER") "Altium Limited"))
      (libsource (lib "Miscellaneous Devices") (part "Res3"))
    )
    (comp (ref "R266")
      (value "4.7k")
      (footprint "J1-0603")
      (description "Resistor")
      (fields (field (name "Comment") "Res3") (field (name "PUBLISHER") "Altium Limited"))
      (libsource (lib "Miscellaneous Devices") (part "Res3"))
    )
    (comp (ref "R267")
      (value "100")
      (footprint "J1-0603")
      (description "Resistor")
      (fields (field (name "Comment") "Res3") (field (name "PUBLISHER") "Altium Limited"))
      (libsource (lib "Miscellaneous Devices") (part "Res3"))
    )
    (comp (ref "R268")
      (value "4.7k")
      (footprint "J1-0603")
      (description "Resistor")
      (fields (field (name "Comment") "Res3") (field (name "PUBLISHER") "Altium Limited"))
      (libsource (lib "Miscellaneous Devices") (part "Res3"))
    )
    (comp (ref "R270")
      (value "4.7k")
      (footprint "J1-0603")
      (description "Resistor")
      (fields (field (name "Comment") "Res3") (field (name "PUBLISHER") "Altium Limited"))
      (libsource (lib "Miscellaneous Devices") (part "Res3"))
    )
    (comp (ref "R271")
      (value "100")
      (footprint "J1-0603")
      (description "Resistor")
      (fields (field (name "Comment") "Res3") (field (name "PUBLISHER") "Altium Limited"))
      (libsource (lib "Miscellaneous Devices") (part "Res3"))
    )
    (comp (ref "R272")
      (value "4.7k")
      (footprint "J1-0603")
      (description "Resistor")
      (fields (field (name "Comment") "Res3") (field (name "PUBLISHER") "Altium Limited"))
      (libsource (lib "Miscellaneous Devices") (part "Res3"))
    )
    (comp (ref "R274")
      (value "4.7k")
      (footprint "J1-0603")
      (description "Resistor")
      (fields (field (name "Comment") "Res3") (field (name "PUBLISHER") "Altium Limited"))
      (libsource (lib "Miscellaneous Devices") (part "Res3"))
    )
    (comp (ref "R275")
      (value "100")
      (footprint "J1-0603")
      (description "Resistor")
      (fields (field (name "Comment") "Res3") (field (name "PUBLISHER") "Altium Limited"))
      (libsource (lib "Miscellaneous Devices") (part "Res3"))
    )
    (comp (ref "R276")
      (value "4.7k")
      (footprint "J1-0603")
      (description "Resistor")
      (fields (field (name "Comment") "Res3") (field (name "PUBLISHER") "Altium Limited"))
      (libsource (lib "Miscellaneous Devices") (part "Res3"))
    )
    (comp (ref "R277")
      (value "4.7k")
      (footprint "J1-0603")
      (description "Resistor")
      (fields (field (name "Comment") "Res3") (field (name "PUBLISHER") "Altium Limited"))
      (libsource (lib "Miscellaneous Devices") (part "Res3"))
    )
    (comp (ref "R278")
      (value "1.5k")
      (footprint "J1-0603")
      (description "Resistor")
      (fields (field (name "Comment") "Res3") (field (name "PUBLISHER") "Altium Limited"))
      (libsource (lib "Miscellaneous Devices") (part "Res3"))
    )
    (comp (ref "R279")
      (value "1.5k")
      (footprint "J1-0603")
      (description "Resistor")
      (fields (field (name "Comment") "Res3") (field (name "PUBLISHER") "Altium Limited"))
      (libsource (lib "Miscellaneous Devices") (part "Res3"))
    )
    (comp (ref "R280")
      (value "1.5k")
      (footprint "J1-0603")
      (description "Resistor")
      (fields (field (name "Comment") "Res3") (field (name "PUBLISHER") "Altium Limited"))
      (libsource (lib "Miscellaneous Devices") (part "Res3"))
    )
    (comp (ref "R281")
      (value "1.5k")
      (footprint "J1-0603")
      (description "Resistor")
      (fields (field (name "Comment") "Res3") (field (name "PUBLISHER") "Altium Limited"))
      (libsource (lib "Miscellaneous Devices") (part "Res3"))
    )
    (comp (ref "R282")
      (value "1.5k")
      (footprint "J1-0603")
      (description "Resistor")
      (fields (field (name "Comment") "Res3") (field (name "PUBLISHER") "Altium Limited"))
      (libsource (lib "Miscellaneous Devices") (part "Res3"))
    )
    (comp (ref "R283")
      (value "1.5k")
      (footprint "J1-0603")
      (description "Resistor")
      (fields (field (name "Comment") "Res3") (field (name "PUBLISHER") "Altium Limited"))
      (libsource (lib "Miscellaneous Devices") (part "Res3"))
    )
    (comp (ref "R284")
      (value "1.5k")
      (footprint "J1-0603")
      (description "Resistor")
      (fields (field (name "Comment") "Res3") (field (name "PUBLISHER") "Altium Limited"))
      (libsource (lib "Miscellaneous Devices") (part "Res3"))
    )
    (comp (ref "R285")
      (value "1.5k")
      (footprint "J1-0603")
      (description "Resistor")
      (fields (field (name "Comment") "Res3") (field (name "PUBLISHER") "Altium Limited"))
      (libsource (lib "Miscellaneous Devices") (part "Res3"))
    )
    (comp (ref "R286")
      (value "1.5k")
      (footprint "J1-0603")
      (description "Resistor")
      (fields (field (name "Comment") "Res3") (field (name "PUBLISHER") "Altium Limited"))
      (libsource (lib "Miscellaneous Devices") (part "Res3"))
    )
    (comp (ref "R287")
      (value "1.5k")
      (footprint "J1-0603")
      (description "Resistor")
      (fields (field (name "Comment") "Res3") (field (name "PUBLISHER") "Altium Limited"))
      (libsource (lib "Miscellaneous Devices") (part "Res3"))
    )
    (comp (ref "R288")
      (value "1.5k")
      (footprint "J1-0603")
      (description "Resistor")
      (fields (field (name "Comment") "Res3") (field (name "PUBLISHER") "Altium Limited"))
      (libsource (lib "Miscellaneous Devices") (part "Res3"))
    )
    (comp (ref "R289")
      (value "1.5k")
      (footprint "J1-0603")
      (description "Resistor")
      (fields (field (name "Comment") "Res3") (field (name "PUBLISHER") "Altium Limited"))
      (libsource (lib "Miscellaneous Devices") (part "Res3"))
    )
    (comp (ref "R290")
      (value "1.5k")
      (footprint "J1-0603")
      (description "Resistor")
      (fields (field (name "Comment") "Res3") (field (name "PUBLISHER") "Altium Limited"))
      (libsource (lib "Miscellaneous Devices") (part "Res3"))
    )
    (comp (ref "R291")
      (value "1.5k")
      (footprint "J1-0603")
      (description "Resistor")
      (fields (field (name "Comment") "Res3") (field (name "PUBLISHER") "Altium Limited"))
      (libsource (lib "Miscellaneous Devices") (part "Res3"))
    )
    (comp (ref "R292")
      (value "1.5k")
      (footprint "J1-0603")
      (description "Resistor")
      (fields (field (name "Comment") "Res3") (field (name "PUBLISHER") "Altium Limited"))
      (libsource (lib "Miscellaneous Devices") (part "Res3"))
    )
    (comp (ref "R293")
      (value "1.5k")
      (footprint "J1-0603")
      (description "Resistor")
      (fields (field (name "Comment") "Res3") (field (name "PUBLISHER") "Altium Limited"))
      (libsource (lib "Miscellaneous Devices") (part "Res3"))
    )
    (comp (ref "R294")
      (value "1.5k")
      (footprint "J1-0603")
      (description "Resistor")
      (fields (field (name "Comment") "Res3") (field (name "PUBLISHER") "Altium Limited"))
      (libsource (lib "Miscellaneous Devices") (part "Res3"))
    )
    (comp (ref "R295")
      (value "1.5k")
      (footprint "J1-0603")
      (description "Resistor")
      (fields (field (name "Comment") "Res3") (field (name "PUBLISHER") "Altium Limited"))
      (libsource (lib "Miscellaneous Devices") (part "Res3"))
    )
    (comp (ref "R296")
      (value "1.5k")
      (footprint "J1-0603")
      (description "Resistor")
      (fields (field (name "Comment") "Res3") (field (name "PUBLISHER") "Altium Limited"))
      (libsource (lib "Miscellaneous Devices") (part "Res3"))
    )
    (comp (ref "R297")
      (value "1.5k")
      (footprint "J1-0603")
      (description "Resistor")
      (fields (field (name "Comment") "Res3") (field (name "PUBLISHER") "Altium Limited"))
      (libsource (lib "Miscellaneous Devices") (part "Res3"))
    )
    (comp (ref "R298")
      (value "1.5k")
      (footprint "J1-0603")
      (description "Resistor")
      (fields (field (name "Comment") "Res3") (field (name "PUBLISHER") "Altium Limited"))
      (libsource (lib "Miscellaneous Devices") (part "Res3"))
    )
    (comp (ref "R299")
      (value "1.5k")
      (footprint "J1-0603")
      (description "Resistor")
      (fields (field (name "Comment") "Res3") (field (name "PUBLISHER") "Altium Limited"))
      (libsource (lib "Miscellaneous Devices") (part "Res3"))
    )
    (comp (ref "R300")
      (value "4.7k")
      (footprint "J1-0603")
      (description "Resistor")
      (fields (field (name "Comment") "Res3") (field (name "PUBLISHER") "Altium Limited"))
      (libsource (lib "Miscellaneous Devices") (part "Res3"))
    )
    (comp (ref "R301")
      (value "4.7k")
      (footprint "J1-0603")
      (description "Resistor")
      (fields (field (name "Comment") "Res3") (field (name "PUBLISHER") "Altium Limited"))
      (libsource (lib "Miscellaneous Devices") (part "Res3"))
    )
    (comp (ref "R302")
      (value "4.7k")
      (footprint "J1-0603")
      (description "Resistor")
      (fields (field (name "Comment") "Res3") (field (name "PUBLISHER") "Altium Limited"))
      (libsource (lib "Miscellaneous Devices") (part "Res3"))
    )
    (comp (ref "R303")
      (value "100")
      (footprint "J1-0603")
      (description "Resistor")
      (fields (field (name "Comment") "Res3") (field (name "PUBLISHER") "Altium Limited"))
      (libsource (lib "Miscellaneous Devices") (part "Res3"))
    )
    (comp (ref "R304")
      (value "4.7k")
      (footprint "J1-0603")
      (description "Resistor")
      (fields (field (name "Comment") "Res3") (field (name "PUBLISHER") "Altium Limited"))
      (libsource (lib "Miscellaneous Devices") (part "Res3"))
    )
    (comp (ref "R305")
      (value "4.7k")
      (footprint "J1-0603")
      (description "Resistor")
      (fields (field (name "Comment") "Res3") (field (name "PUBLISHER") "Altium Limited"))
      (libsource (lib "Miscellaneous Devices") (part "Res3"))
    )
    (comp (ref "R306")
      (value "4.7k")
      (footprint "J1-0603")
      (description "Resistor")
      (fields (field (name "Comment") "Res3") (field (name "PUBLISHER") "Altium Limited"))
      (libsource (lib "Miscellaneous Devices") (part "Res3"))
    )
    (comp (ref "R307")
      (value "100")
      (footprint "J1-0603")
      (description "Resistor")
      (fields (field (name "Comment") "Res3") (field (name "PUBLISHER") "Altium Limited"))
      (libsource (lib "Miscellaneous Devices") (part "Res3"))
    )
    (comp (ref "R308")
      (value "100")
      (footprint "J1-0603")
      (description "Resistor")
      (fields (field (name "Comment") "Res3") (field (name "PUBLISHER") "Altium Limited"))
      (libsource (lib "Miscellaneous Devices") (part "Res3"))
    )
    (comp (ref "R309")
      (value "100")
      (footprint "J1-0603")
      (description "Resistor")
      (fields (field (name "Comment") "Res3") (field (name "PUBLISHER") "Altium Limited"))
      (libsource (lib "Miscellaneous Devices") (part "Res3"))
    )
    (comp (ref "R310")
      (value "4.7k")
      (footprint "J1-0603")
      (description "Resistor")
      (fields (field (name "Comment") "Res3") (field (name "PUBLISHER") "Altium Limited"))
      (libsource (lib "Miscellaneous Devices") (part "Res3"))
    )
    (comp (ref "R311")
      (value "Res3")
      (footprint "J1-0603")
      (description "Resistor")
      (fields
        (field (name "ALTIUM_VALUE") "1.5K")
        (field (name "SUPPLIER PART NUMBER 1") "RMCF0603JT1K50CT-ND")
        (field (name "PUBLISHER") "Altium Limited")
      )
      (libsource (lib "Miscellaneous Devices") (part "Res3"))
    )
    (comp (ref "R368")
      (value "Res3")
      (footprint "J1-0603")
      (description "Resistor")
      (fields (field (name "ALTIUM_VALUE") "4.7K") (field (name "PUBLISHER") "Altium Limited"))
      (libsource (lib "Miscellaneous Devices") (part "Res3"))
    )
    (comp (ref "U20")
      (value "XC6SLX9-3TQG144C")
      (footprint "TQG144_N")
      (fields (field (name "SUPPLIER PART NUMBER 1") "122-1747-ND"))
      (libsource (lib "Xilinx Spartan-6") (part "XC6SLX9-3TQG144C"))
    )
    (comp (ref "U21")
      (value "MC74HC595A_TSSOP16")
      (footprint "MC74HC595A_TSSOP16")
      (fields (field (name "SUPPLIER PART NUMBER 1") "MC74HC595ADTR2GOSCT-ND"))
      (libsource (lib "Lib1") (part "MC74HC595A_TSSOP16"))
    )
    (comp (ref "U22")
      (value "MC74HC595A_TSSOP16")
      (footprint "MC74HC595A_TSSOP16")
      (fields (field (name "SUPPLIER PART NUMBER 1") "MC74HC595ADTR2GOSCT-ND"))
      (libsource (lib "Lib1") (part "MC74HC595A_TSSOP16"))
    )
    (comp (ref "U23")
      (value "MC74HC595A_TSSOP16")
      (footprint "MC74HC595A_TSSOP16")
      (fields (field (name "SUPPLIER PART NUMBER 1") "MC74HC595ADTR2GOSCT-ND"))
      (libsource (lib "Lib1") (part "MC74HC595A_TSSOP16"))
    )
    (comp (ref "U24")
      (value "M25P16-VMN6P")
      (footprint "MICT-MN-8_N")
      (description "16 Mb (x1) Serial NOR Flash Memory, 75 MHz, 2.7 to 3.6 V, 8-pin SO8 Narrow (MN), Tube")
      (fields
        (field (name "VOLTAGE") "2.7V-3.6V ")
        (field (name "MANUFACTURER") "Micron")
        (field (name "SUPPLIER PART NUMBER 1") "M25P16-VMN6P-ND")
      )
      (libsource (lib "Micron-Memory-Serial-NOR-Flash") (part "M25P16-VMN6P"))
    )
  )
  (nets
    (net (code "1") (name "/CCLK") (class "Default")
      (node (ref "P22") (pin "1") (pinfunction "1_1") (pintype "passive"))
      (node (ref "R156") (pin "2") (pinfunction "2_2") (pintype "passive"))
      (node (ref "R157") (pin "2") (pinfunction "2_2") (pintype "passive"))
      (node (ref "R307") (pin "1") (pinfunction "1_1") (pintype "passive"))
      (node (ref "U20") (pin "70") (pinfunction "IO_L1P_CCLK_2_70") (pintype "bidirectional"))
    )
    (net (code "2") (name "/CLK") (class "Default")
      (node (ref "R368") (pin "1") (pinfunction "1_1") (pintype "passive"))
      (node (ref "U20") (pin "16") (pinfunction "IO_L43N_GCLK22_IRDY2_3_16") (pintype "bidirectional"))
    )
    (net (code "3") (name "/CONFIG1") (class "Default")
      (node (ref "P19") (pin "1") (pinfunction "1_1") (pintype "passive"))
      (node (ref "R166") (pin "1") (pinfunction "1_1") (pintype "passive"))
      (node (ref "R294") (pin "1") (pinfunction "1_1") (pintype "passive"))
      (node (ref "U20") (pin "105") (pinfunction "IO_L1P_1_105") (pintype "bidirectional"))
    )
    (net (code "4") (name "/CONFIG2") (class "Default")
      (node (ref "P19") (pin "3") (pinfunction "3_3") (pintype "passive"))
      (node (ref "R171") (pin "1") (pinfunction "1_1") (pintype "passive"))
      (node (ref "R296") (pin "1") (pinfunction "1_1") (pintype "passive"))
      (node (ref "U20") (pin "104") (pinfunction "IO_L1N_VREF_1_104") (pintype "bidirectional"))
    )
    (net (code "5") (name "/CONFIG3") (class "Default")
      (node (ref "P19") (pin "5") (pinfunction "5_5") (pintype "passive"))
      (node (ref "R176") (pin "1") (pinfunction "1_1") (pintype "passive"))
      (node (ref "R298") (pin "1") (pinfunction "1_1") (pintype "passive"))
      (node (ref "U20") (pin "102") (pinfunction "IO_L32P_1_102") (pintype "bidirectional"))
    )
    (net (code "6") (name "/CONFIG4") (class "Default")
      (node (ref "P19") (pin "7") (pinfunction "7_7") (pintype "passive"))
      (node (ref "R181") (pin "1") (pinfunction "1_1") (pintype "passive"))
      (node (ref "R299") (pin "1") (pinfunction "1_1") (pintype "passive"))
      (node (ref "U20") (pin "101") (pinfunction "IO_L32N_1_101") (pintype "bidirectional"))
    )
    (net (code "7") (name "/D1V2") (class "Default")
      (node (ref "C82") (pin "1") (pinfunction "1_1") (pintype "passive"))
      (node (ref "C83") (pin "1") (pinfunction "1_1") (pintype "passive"))
      (node (ref "C84") (pin "1") (pinfunction "1_1") (pintype "passive"))
      (node (ref "C85") (pin "1") (pinfunction "1_1") (pintype "passive"))
      (node (ref "U20") (pin "128") (pinfunction "VCCINT_128") (pintype "power_in"))
      (node (ref "U20") (pin "19") (pinfunction "VCCINT_19") (pintype "power_in"))
      (node (ref "U20") (pin "28") (pinfunction "VCCINT_28") (pintype "power_in"))
      (node (ref "U20") (pin "52") (pinfunction "VCCINT_52") (pintype "power_in"))
      (node (ref "U20") (pin "89") (pinfunction "VCCINT_89") (pintype "power_in"))
    )
    (net (code "8") (name "/D3V3") (class "Default")
      (node (ref "C64") (pin "1") (pinfunction "1_1") (pintype "passive"))
      (node (ref "C65") (pin "1") (pinfunction "1_1") (pintype "passive"))
      (node (ref "C66") (pin "1") (pinfunction "1_1") (pintype "passive"))
      (node (ref "C67") (pin "1") (pinfunction "1_1") (pintype "passive"))
      (node (ref "C68") (pin "1") (pinfunction "1_1") (pintype "passive"))
      (node (ref "C69") (pin "1") (pinfunction "1_1") (pintype "passive"))
      (node (ref "C70") (pin "1") (pinfunction "1_1") (pintype "passive"))
      (node (ref "C71") (pin "1") (pinfunction "1_1") (pintype "passive"))
      (node (ref "C72") (pin "1") (pinfunction "1_1") (pintype "passive"))
      (node (ref "C73") (pin "1") (pinfunction "1_1") (pintype "passive"))
      (node (ref "C74") (pin "1") (pinfunction "1_1") (pintype "passive"))
      (node (ref "C75") (pin "1") (pinfunction "1_1") (pintype "passive"))
      (node (ref "C76") (pin "1") (pinfunction "1_1") (pintype "passive"))
      (node (ref "C77") (pin "1") (pinfunction "1_1") (pintype "passive"))
      (node (ref "C78") (pin "1") (pinfunction "1_1") (pintype "passive"))
      (node (ref "C79") (pin "1") (pinfunction "1_1") (pintype "passive"))
      (node (ref "C80") (pin "1") (pinfunction "1_1") (pintype "passive"))
      (node (ref "C81") (pin "2") (pinfunction "2_2") (pintype "passive"))
      (node (ref "C86") (pin "1") (pinfunction "1_1") (pintype "passive"))
      (node (ref "C87") (pin "1") (pinfunction "1_1") (pintype "passive"))
      (node (ref "C88") (pin "1") (pinfunction "1_1") (pintype "passive"))
      (node (ref "C89") (pin "1") (pinfunction "1_1") (pintype "passive"))
      (node (ref "C90") (pin "1") (pinfunction "1_1") (pintype "passive"))
      (node (ref "C91") (pin "1") (pinfunction "1_1") (pintype "passive"))
      (node (ref "C92") (pin "1") (pinfunction "1_1") (pintype "passive"))
      (node (ref "LED31") (pin "1") (pinfunction "1_1") (pintype "passive"))
      (node (ref "OSC1") (pin "1") (pinfunction "E/D_1") (pintype "passive"))
      (node (ref "OSC1") (pin "4") (pinfunction "VDD_4") (pintype "passive"))
      (node (ref "P19") (pin "2") (pinfunction "2_2") (pintype "passive"))
      (node (ref "P19") (pin "4") (pinfunction "4_4") (pintype "passive"))
      (node (ref "P19") (pin "6") (pinfunction "6_6") (pintype "passive"))
      (node (ref "P19") (pin "8") (pinfunction "8_8") (pintype "passive"))
      (node (ref "P21") (pin "6") (pinfunction "6_6") (pintype "passive"))
      (node (ref "R153") (pin "2") (pinfunction "2_2") (pintype "passive"))
      (node (ref "R154") (pin "2") (pinfunction "2_2") (pintype "passive"))
      (node (ref "R155") (pin "2") (pinfunction "2_2") (pintype "passive"))
      (node (ref "R156") (pin "1") (pinfunction "1_1") (pintype "passive"))
      (node (ref "R190") (pin "2") (pinfunction "2_2") (pintype "passive"))
      (node (ref "R195") (pin "2") (pinfunction "2_2") (pintype "passive"))
      (node (ref "R200") (pin "2") (pinfunction "2_2") (pintype "passive"))
      (node (ref "R215") (pin "2") (pinfunction "2_2") (pintype "passive"))
      (node (ref "R239") (pin "2") (pinfunction "2_2") (pintype "passive"))
      (node (ref "R244") (pin "2") (pinfunction "2_2") (pintype "passive"))
      (node (ref "R249") (pin "2") (pinfunction "2_2") (pintype "passive"))
      (node (ref "R255") (pin "2") (pinfunction "2_2") (pintype "passive"))
      (node (ref "R260") (pin "2") (pinfunction "2_2") (pintype "passive"))
      (node (ref "R264") (pin "2") (pinfunction "2_2") (pintype "passive"))
      (node (ref "R268") (pin "2") (pinfunction "2_2") (pintype "passive"))
      (node (ref "R272") (pin "2") (pinfunction "2_2") (pintype "passive"))
      (node (ref "R276") (pin "2") (pinfunction "2_2") (pintype "passive"))
      (node (ref "R300") (pin "1") (pinfunction "1_1") (pintype "passive"))
      (node (ref "R301") (pin "1") (pinfunction "1_1") (pintype "passive"))
      (node (ref "R302") (pin "1") (pinfunction "1_1") (pintype "passive"))
      (node (ref "R304") (pin "1") (pinfunction "1_1") (pintype "passive"))
      (node (ref "R305") (pin "1") (pinfunction "1_1") (pintype "passive"))
      (node (ref "R306") (pin "1") (pinfunction "1_1") (pintype "passive"))
      (node (ref "R310") (pin "2") (pinfunction "2_2") (pintype "passive"))
      (node (ref "U20") (pin "103") (pinfunction "VCCO_1_103") (pintype "power_in"))
      (node (ref "U20") (pin "122") (pinfunction "VCCO_0_122") (pintype "power_in"))
      (node (ref "U20") (pin "125") (pinfunction "VCCO_0_125") (pintype "power_in"))
      (node (ref "U20") (pin "129") (pinfunction "VCCAUX_129") (pintype "power_in"))
      (node (ref "U20") (pin "135") (pinfunction "VCCO_0_135") (pintype "power_in"))
      (node (ref "U20") (pin "18") (pinfunction "VCCO_3_18") (pintype "power_in"))
      (node (ref "U20") (pin "20") (pinfunction "VCCAUX_20") (pintype "power_in"))
      (node (ref "U20") (pin "31") (pinfunction "VCCO_3_31") (pintype "power_in"))
      (node (ref "U20") (pin "36") (pinfunction "VCCAUX_36") (pintype "power_in"))
      (node (ref "U20") (pin "4") (pinfunction "VCCO_3_4") (pintype "power_in"))
      (node (ref "U20") (pin "42") (pinfunction "VCCO_2_42") (pintype "power_in"))
      (node (ref "U20") (pin "53") (pinfunction "VCCAUX_53") (pintype "power_in"))
      (node (ref "U20") (pin "63") (pinfunction "VCCO_2_63") (pintype "power_in"))
      (node (ref "U20") (pin "76") (pinfunction "VCCO_1_76") (pintype "power_in"))
      (node (ref "U20") (pin "86") (pinfunction "VCCO_1_86") (pintype "power_in"))
      (node (ref "U20") (pin "90") (pinfunction "VCCAUX_90") (pintype "power_in"))
      (node (ref "U21") (pin "16") (pinfunction "VCC_16") (pintype "passive"))
      (node (ref "U22") (pin "16") (pinfunction "VCC_16") (pintype "passive"))
      (node (ref "U23") (pin "16") (pinfunction "VCC_16") (pintype "passive"))
      (node (ref "U24") (pin "8") (pinfunction "VCC_8") (pintype "power_in"))
    )
    (net (code "9") (name "/DEBUG1") (class "Default")
      (node (ref "P20") (pin "1") (pinfunction "1_1") (pintype "passive"))
      (node (ref "U20") (pin "123") (pinfunction "IO_L37N_GCLK12_0_123") (pintype "bidirectional"))
    )
    (net (code "10") (name "/DEBUG2") (class "Default")
      (node (ref "P20") (pin "2") (pinfunction "2_2") (pintype "passive"))
      (node (ref "U20") (pin "121") (pinfunction "IO_L62P_0_121") (pintype "bidirectional"))
    )
    (net (code "11") (name "/DEBUG3") (class "Default")
      (node (ref "P20") (pin "3") (pinfunction "3_3") (pintype "passive"))
      (node (ref "U20") (pin "120") (pinfunction "IO_L62N_VREF_0_120") (pintype "bidirectional"))
    )
    (net (code "12") (name "/DEBUG4") (class "Default")
      (node (ref "P20") (pin "4") (pinfunction "4_4") (pintype "passive"))
      (node (ref "U20") (pin "119") (pinfunction "IO_L63P_SCP7_0_119") (pintype "bidirectional"))
    )
    (net (code "13") (name "/DEBUG5") (class "Default")
      (node (ref "P20") (pin "5") (pinfunction "5_5") (pintype "passive"))
      (node (ref "U20") (pin "118") (pinfunction "IO_L63N_SCP6_0_118") (pintype "bidirectional"))
    )
    (net (code "14") (name "/DEBUG6") (class "Default")
      (node (ref "P20") (pin "6") (pinfunction "6_6") (pintype "passive"))
      (node (ref "U20") (pin "117") (pinfunction "IO_L64P_SCP5_0_117") (pintype "bidirectional"))
    )
    (net (code "15") (name "/DEBUG7") (class "Default")
      (node (ref "P20") (pin "7") (pinfunction "7_7") (pintype "passive"))
      (node (ref "U20") (pin "116") (pinfunction "IO_L64N_SCP4_0_116") (pintype "bidirectional"))
    )
    (net (code "16") (name "/DEBUG8") (class "Default")
      (node (ref "P20") (pin "8") (pinfunction "8_8") (pintype "passive"))
      (node (ref "U20") (pin "115") (pinfunction "IO_L65P_SCP3_0_115") (pintype "bidirectional"))
    )
    (net (code "17") (name "/DEBUG9") (class "Default")
      (node (ref "P20") (pin "9") (pinfunction "9_9") (pintype "passive"))
      (node (ref "U20") (pin "114") (pinfunction "IO_L65N_SCP2_0_114") (pintype "bidirectional"))
    )
    (net (code "18") (name "/DEBUG10") (class "Default")
      (node (ref "P20") (pin "10") (pinfunction "10_10") (pintype "passive"))
      (node (ref "U20") (pin "112") (pinfunction "IO_L66P_SCP1_0_112") (pintype "bidirectional"))
    )
    (net (code "19") (name "/DIN") (class "Default")
      (node (ref "P22") (pin "2") (pinfunction "2_2") (pintype "passive"))
      (node (ref "R300") (pin "2") (pinfunction "2_2") (pintype "passive"))
      (node (ref "R309") (pin "1") (pinfunction "1_1") (pintype "passive"))
      (node (ref "U20") (pin "65") (pinfunction "IO_L3P_D0_DIN_MISO_MISO1_2_65") (pintype "bidirectional"))
    )
    (net (code "20") (name "/DONE") (class "Default")
      (node (ref "R311") (pin "2") (pinfunction "2_2") (pintype "passive"))
      (node (ref "U20") (pin "71") (pinfunction "DONE_2_71") (pintype "bidirectional"))
    )
    (net (code "21") (name "/EN1") (class "Default")
      (node (ref "R165") (pin "1") (pinfunction "1_1") (pintype "passive"))
      (node (ref "R278") (pin "1") (pinfunction "1_1") (pintype "passive"))
      (node (ref "U22") (pin "4") (pinfunction "QE_4") (pintype "passive"))
    )
    (net (code "22") (name "/EN2") (class "Default")
      (node (ref "R169") (pin "1") (pinfunction "1_1") (pintype "passive"))
      (node (ref "R279") (pin "1") (pinfunction "1_1") (pintype "passive"))
      (node (ref "U22") (pin "3") (pinfunction "QD_3") (pintype "passive"))
    )
    (net (code "23") (name "/EN3") (class "Default")
      (node (ref "R174") (pin "1") (pinfunction "1_1") (pintype "passive"))
      (node (ref "R280") (pin "1") (pinfunction "1_1") (pintype "passive"))
      (node (ref "U22") (pin "2") (pinfunction "QC_2") (pintype "passive"))
    )
    (net (code "24") (name "/EN4") (class "Default")
      (node (ref "R179") (pin "1") (pinfunction "1_1") (pintype "passive"))
      (node (ref "R281") (pin "1") (pinfunction "1_1") (pintype "passive"))
      (node (ref "U22") (pin "1") (pinfunction "QB_1") (pintype "passive"))
    )
    (net (code "25") (name "/EN5") (class "Default")
      (node (ref "R184") (pin "1") (pinfunction "1_1") (pintype "passive"))
      (node (ref "R282") (pin "1") (pinfunction "1_1") (pintype "passive"))
      (node (ref "U21") (pin "2") (pinfunction "QC_2") (pintype "passive"))
    )
    (net (code "26") (name "/EN6") (class "Default")
      (node (ref "R189") (pin "1") (pinfunction "1_1") (pintype "passive"))
      (node (ref "R283") (pin "1") (pinfunction "1_1") (pintype "passive"))
      (node (ref "U21") (pin "1") (pinfunction "QB_1") (pintype "passive"))
    )
    (net (code "27") (name "/EN7") (class "Default")
      (node (ref "R194") (pin "1") (pinfunction "1_1") (pintype "passive"))
      (node (ref "R284") (pin "1") (pinfunction "1_1") (pintype "passive"))
      (node (ref "U21") (pin "15") (pinfunction "QA_15") (pintype "passive"))
    )
    (net (code "28") (name "/EN8") (class "Default")
      (node (ref "R199") (pin "1") (pinfunction "1_1") (pintype "passive"))
      (node (ref "R285") (pin "1") (pinfunction "1_1") (pintype "passive"))
      (node (ref "U22") (pin "7") (pinfunction "QH_7") (pintype "passive"))
    )
    (net (code "29") (name "/EN9") (class "Default")
      (node (ref "R204") (pin "1") (pinfunction "1_1") (pintype "passive"))
      (node (ref "R286") (pin "1") (pinfunction "1_1") (pintype "passive"))
      (node (ref "U21") (pin "7") (pinfunction "QH_7") (pintype "passive"))
    )
    (net (code "30") (name "/EN10") (class "Default")
      (node (ref "R209") (pin "1") (pinfunction "1_1") (pintype "passive"))
      (node (ref "R287") (pin "1") (pinfunction "1_1") (pintype "passive"))
      (node (ref "U21") (pin "4") (pinfunction "QE_4") (pintype "passive"))
    )
    (net (code "31") (name "/EN11") (class "Default")
      (node (ref "R214") (pin "1") (pinfunction "1_1") (pintype "passive"))
      (node (ref "R288") (pin "1") (pinfunction "1_1") (pintype "passive"))
      (node (ref "U22") (pin "5") (pinfunction "QF_5") (pintype "passive"))
    )
    (net (code "32") (name "/EN12") (class "Default")
      (node (ref "R219") (pin "1") (pinfunction "1_1") (pintype "passive"))
      (node (ref "R289") (pin "1") (pinfunction "1_1") (pintype "passive"))
      (node (ref "U23") (pin "7") (pinfunction "QH_7") (pintype "passive"))
    )
    (net (code "33") (name "/EN13") (class "Default")
      (node (ref "R224") (pin "1") (pinfunction "1_1") (pintype "passive"))
      (node (ref "R290") (pin "1") (pinfunction "1_1") (pintype "passive"))
      (node (ref "U23") (pin "5") (pinfunction "QF_5") (pintype "passive"))
    )
    (net (code "35") (name "/EN_RESET1") (class "Default")
      (node (ref "R229") (pin "1") (pinfunction "1_1") (pintype "passive"))
      (node (ref "R291") (pin "1") (pinfunction "1_1") (pintype "passive"))
      (node (ref "U23") (pin "2") (pinfunction "QC_2") (pintype "passive"))
    )
    (net (code "36") (name "/EN_RESET2") (class "Default")
      (node (ref "R234") (pin "1") (pinfunction "1_1") (pintype "passive"))
      (node (ref "R292") (pin "1") (pinfunction "1_1") (pintype "passive"))
      (node (ref "U23") (pin "15") (pinfunction "QA_15") (pintype "passive"))
    )
    (net (code "38") (name "/EOC1") (class "Default")
      (node (ref "U20") (pin "56") (pinfunction "IO_L30P_GCLK1_D13_2_56") (pintype "bidirectional"))
    )
    (net (code "39") (name "/EOC2") (class "Default")
      (node (ref "U20") (pin "111") (pinfunction "IO_L66N_SCP0_0_111") (pintype "bidirectional"))
    )
    (net (code "40") (name "/GCLK") (class "Default")
      (node (ref "C93") (pin "1") (pinfunction "1_1") (pintype "passive"))
      (node (ref "OSC1") (pin "3") (pinfunction "OUT_3") (pintype "passive"))
      (node (ref "U20") (pin "14") (pinfunction "IO_L44N_GCLK20_3_14") (pintype "bidirectional"))
    )
    (net (code "41") (name "/GND") (class "Default")
      (node (ref "C64") (pin "2") (pinfunction "2_2") (pintype "passive"))
      (node (ref "C65") (pin "2") (pinfunction "2_2") (pintype "passive"))
      (node (ref "C66") (pin "2") (pinfunction "2_2") (pintype "passive"))
      (node (ref "C67") (pin "2") (pinfunction "2_2") (pintype "passive"))
      (node (ref "C68") (pin "2") (pinfunction "2_2") (pintype "passive"))
      (node (ref "C69") (pin "2") (pinfunction "2_2") (pintype "passive"))
      (node (ref "C70") (pin "2") (pinfunction "2_2") (pintype "passive"))
      (node (ref "C71") (pin "2") (pinfunction "2_2") (pintype "passive"))
      (node (ref "C72") (pin "2") (pinfunction "2_2") (pintype "passive"))
      (node (ref "C73") (pin "2") (pinfunction "2_2") (pintype "passive"))
      (node (ref "C74") (pin "2") (pinfunction "2_2") (pintype "passive"))
      (node (ref "C75") (pin "2") (pinfunction "2_2") (pintype "passive"))
      (node (ref "C76") (pin "2") (pinfunction "2_2") (pintype "passive"))
      (node (ref "C77") (pin "2") (pinfunction "2_2") (pintype "passive"))
      (node (ref "C78") (pin "2") (pinfunction "2_2") (pintype "passive"))
      (node (ref "C79") (pin "2") (pinfunction "2_2") (pintype "passive"))
      (node (ref "C80") (pin "2") (pinfunction "2_2") (pintype "passive"))
      (node (ref "C81") (pin "1") (pinfunction "1_1") (pintype "passive"))
      (node (ref "C82") (pin "2") (pinfunction "2_2") (pintype "passive"))
      (node (ref "C83") (pin "2") (pinfunction "2_2") (pintype "passive"))
      (node (ref "C84") (pin "2") (pinfunction "2_2") (pintype "passive"))
      (node (ref "C85") (pin "2") (pinfunction "2_2") (pintype "passive"))
      (node (ref "C86") (pin "2") (pinfunction "2_2") (pintype "passive"))
      (node (ref "C87") (pin "2") (pinfunction "2_2") (pintype "passive"))
      (node (ref "C88") (pin "2") (pinfunction "2_2") (pintype "passive"))
      (node (ref "C89") (pin "2") (pinfunction "2_2") (pintype "passive"))
      (node (ref "C90") (pin "2") (pinfunction "2_2") (pintype "passive"))
      (node (ref "C91") (pin "2") (pinfunction "2_2") (pintype "passive"))
      (node (ref "C92") (pin "2") (pinfunction "2_2") (pintype "passive"))
      (node (ref "C93") (pin "2") (pinfunction "2_2") (pintype "passive"))
      (node (ref "LED10") (pin "2") (pinfunction "2_2") (pintype "passive"))
      (node (ref "LED11") (pin "2") (pinfunction "2_2") (pintype "passive"))
      (node (ref "LED12") (pin "2") (pinfunction "2_2") (pintype "passive"))
      (node (ref "LED13") (pin "2") (pinfunction "2_2") (pintype "passive"))
      (node (ref "LED14") (pin "2") (pinfunction "2_2") (pintype "passive"))
      (node (ref "LED15") (pin "2") (pinfunction "2_2") (pintype "passive"))
      (node (ref "LED16") (pin "2") (pinfunction "2_2") (pintype "passive"))
      (node (ref "LED17") (pin "2") (pinfunction "2_2") (pintype "passive"))
      (node (ref "LED18") (pin "2") (pinfunction "2_2") (pintype "passive"))
      (node (ref "LED19") (pin "2") (pinfunction "2_2") (pintype "passive"))
      (node (ref "LED20") (pin "2") (pinfunction "2_2") (pintype "passive"))
      (node (ref "LED21") (pin "2") (pinfunction "2_2") (pintype "passive"))
      (node (ref "LED22") (pin "2") (pinfunction "2_2") (pintype "passive"))
      (node (ref "LED23") (pin "2") (pinfunction "2_2") (pintype "passive"))
      (node (ref "LED24") (pin "2") (pinfunction "2_2") (pintype "passive"))
      (node (ref "LED25") (pin "2") (pinfunction "2_2") (pintype "passive"))
      (node (ref "LED26") (pin "2") (pinfunction "2_2") (pintype "passive"))
      (node (ref "LED27") (pin "2") (pinfunction "2_2") (pintype "passive"))
      (node (ref "LED28") (pin "2") (pinfunction "2_2") (pintype "passive"))
      (node (ref "LED29") (pin "2") (pinfunction "2_2") (pintype "passive"))
      (node (ref "LED30") (pin "2") (pinfunction "2_2") (pintype "passive"))
      (node (ref "LED9") (pin "2") (pinfunction "2_2") (pintype "passive"))
      (node (ref "OSC1") (pin "2") (pinfunction "GND_2") (pintype "passive"))
      (node (ref "P21") (pin "5") (pinfunction "5_5") (pintype "passive"))
      (node (ref "P22") (pin "6") (pinfunction "6_6") (pintype "passive"))
      (node (ref "R157") (pin "1") (pinfunction "1_1") (pintype "passive"))
      (node (ref "R158") (pin "2") (pinfunction "2_2") (pintype "passive"))
      (node (ref "R159") (pin "2") (pinfunction "2_2") (pintype "passive"))
      (node (ref "R160") (pin "2") (pinfunction "2_2") (pintype "passive"))
      (node (ref "R161") (pin "2") (pinfunction "2_2") (pintype "passive"))
      (node (ref "R162") (pin "2") (pinfunction "2_2") (pintype "passive"))
      (node (ref "R163") (pin "2") (pinfunction "2_2") (pintype "passive"))
      (node (ref "R164") (pin "2") (pinfunction "2_2") (pintype "passive"))
      (node (ref "R165") (pin "2") (pinfunction "2_2") (pintype "passive"))
      (node (ref "R166") (pin "2") (pinfunction "2_2") (pintype "passive"))
      (node (ref "R167") (pin "2") (pinfunction "2_2") (pintype "passive"))
      (node (ref "R168") (pin "2") (pinfunction "2_2") (pintype "passive"))
      (node (ref "R169") (pin "2") (pinfunction "2_2") (pintype "passive"))
      (node (ref "R171") (pin "2") (pinfunction "2_2") (pintype "passive"))
      (node (ref "R172") (pin "2") (pinfunction "2_2") (pintype "passive"))
      (node (ref "R173") (pin "2") (pinfunction "2_2") (pintype "passive"))
      (node (ref "R174") (pin "2") (pinfunction "2_2") (pintype "passive"))
      (node (ref "R176") (pin "2") (pinfunction "2_2") (pintype "passive"))
      (node (ref "R177") (pin "2") (pinfunction "2_2") (pintype "passive"))
      (node (ref "R178") (pin "2") (pinfunction "2_2") (pintype "passive"))
      (node (ref "R179") (pin "2") (pinfunction "2_2") (pintype "passive"))
      (node (ref "R181") (pin "2") (pinfunction "2_2") (pintype "passive"))
      (node (ref "R182") (pin "2") (pinfunction "2_2") (pintype "passive"))
      (node (ref "R183") (pin "2") (pinfunction "2_2") (pintype "passive"))
      (node (ref "R184") (pin "2") (pinfunction "2_2") (pintype "passive"))
      (node (ref "R185") (pin "2") (pinfunction "2_2") (pintype "passive"))
      (node (ref "R186") (pin "2") (pinfunction "2_2") (pintype "passive"))
      (node (ref "R187") (pin "2") (pinfunction "2_2") (pintype "passive"))
      (node (ref "R188") (pin "2") (pinfunction "2_2") (pintype "passive"))
      (node (ref "R189") (pin "2") (pinfunction "2_2") (pintype "passive"))
      (node (ref "R191") (pin "2") (pinfunction "2_2") (pintype "passive"))
      (node (ref "R192") (pin "2") (pinfunction "2_2") (pintype "passive"))
      (node (ref "R193") (pin "2") (pinfunction "2_2") (pintype "passive"))
      (node (ref "R194") (pin "2") (pinfunction "2_2") (pintype "passive"))
      (node (ref "R196") (pin "2") (pinfunction "2_2") (pintype "passive"))
      (node (ref "R197") (pin "2") (pinfunction "2_2") (pintype "passive"))
      (node (ref "R198") (pin "2") (pinfunction "2_2") (pintype "passive"))
      (node (ref "R199") (pin "2") (pinfunction "2_2") (pintype "passive"))
      (node (ref "R201") (pin "2") (pinfunction "2_2") (pintype "passive"))
      (node (ref "R202") (pin "2") (pinfunction "2_2") (pintype "passive"))
      (node (ref "R203") (pin "2") (pinfunction "2_2") (pintype "passive"))
      (node (ref "R204") (pin "2") (pinfunction "2_2") (pintype "passive"))
      (node (ref "R205") (pin "2") (pinfunction "2_2") (pintype "passive"))
      (node (ref "R206") (pin "2") (pinfunction "2_2") (pintype "passive"))
      (node (ref "R207") (pin "2") (pinfunction "2_2") (pintype "passive"))
      (node (ref "R208") (pin "2") (pinfunction "2_2") (pintype "passive"))
      (node (ref "R209") (pin "2") (pinfunction "2_2") (pintype "passive"))
      (node (ref "R210") (pin "2") (pinfunction "2_2") (pintype "passive"))
      (node (ref "R211") (pin "2") (pinfunction "2_2") (pintype "passive"))
      (node (ref "R212") (pin "2") (pinfunction "2_2") (pintype "passive"))
      (node (ref "R213") (pin "2") (pinfunction "2_2") (pintype "passive"))
      (node (ref "R214") (pin "2") (pinfunction "2_2") (pintype "passive"))
      (node (ref "R216") (pin "2") (pinfunction "2_2") (pintype "passive"))
      (node (ref "R217") (pin "2") (pinfunction "2_2") (pintype "passive"))
      (node (ref "R218") (pin "2") (pinfunction "2_2") (pintype "passive"))
      (node (ref "R219") (pin "2") (pinfunction "2_2") (pintype "passive"))
      (node (ref "R220") (pin "2") (pinfunction "2_2") (pintype "passive"))
      (node (ref "R221") (pin "2") (pinfunction "2_2") (pintype "passive"))
      (node (ref "R222") (pin "2") (pinfunction "2_2") (pintype "passive"))
      (node (ref "R223") (pin "2") (pinfunction "2_2") (pintype "passive"))
      (node (ref "R224") (pin "2") (pinfunction "2_2") (pintype "passive"))
      (node (ref "R225") (pin "2") (pinfunction "2_2") (pintype "passive"))
      (node (ref "R226") (pin "2") (pinfunction "2_2") (pintype "passive"))
      (node (ref "R227") (pin "2") (pinfunction "2_2") (pintype "passive"))
      (node (ref "R228") (pin "2") (pinfunction "2_2") (pintype "passive"))
      (node (ref "R229") (pin "2") (pinfunction "2_2") (pintype "passive"))
      (node (ref "R231") (pin "2") (pinfunction "2_2") (pintype "passive"))
      (node (ref "R232") (pin "2") (pinfunction "2_2") (pintype "passive"))
      (node (ref "R233") (pin "2") (pinfunction "2_2") (pintype "passive"))
      (node (ref "R234") (pin "2") (pinfunction "2_2") (pintype "passive"))
      (node (ref "R236") (pin "2") (pinfunction "2_2") (pintype "passive"))
      (node (ref "R237") (pin "2") (pinfunction "2_2") (pintype "passive"))
      (node (ref "R241") (pin "2") (pinfunction "2_2") (pintype "passive"))
      (node (ref "R242") (pin "2") (pinfunction "2_2") (pintype "passive"))
      (node (ref "R243") (pin "2") (pinfunction "2_2") (pintype "passive"))
      (node (ref "R246") (pin "2") (pinfunction "2_2") (pintype "passive"))
      (node (ref "R247") (pin "2") (pinfunction "2_2") (pintype "passive"))
      (node (ref "R248") (pin "2") (pinfunction "2_2") (pintype "passive"))
      (node (ref "R251") (pin "2") (pinfunction "2_2") (pintype "passive"))
      (node (ref "R252") (pin "2") (pinfunction "2_2") (pintype "passive"))
      (node (ref "R253") (pin "2") (pinfunction "2_2") (pintype "passive"))
      (node (ref "R257") (pin "2") (pinfunction "2_2") (pintype "passive"))
      (node (ref "R258") (pin "2") (pinfunction "2_2") (pintype "passive"))
      (node (ref "R262") (pin "2") (pinfunction "2_2") (pintype "passive"))
      (node (ref "R266") (pin "2") (pinfunction "2_2") (pintype "passive"))
      (node (ref "R270") (pin "2") (pinfunction "2_2") (pintype "passive"))
      (node (ref "R274") (pin "2") (pinfunction "2_2") (pintype "passive"))
      (node (ref "R277") (pin "2") (pinfunction "2_2") (pintype "passive"))
      (node (ref "R368") (pin "2") (pinfunction "2_2") (pintype "passive"))
      (node (ref "U20") (pin "108") (pinfunction "GND_108") (pintype "power_in"))
      (node (ref "U20") (pin "113") (pinfunction "GND_113") (pintype "power_in"))
      (node (ref "U20") (pin "13") (pinfunction "GND_13") (pintype "power_in"))
      (node (ref "U20") (pin "130") (pinfunction "GND_130") (pintype "power_in"))
      (node (ref "U20") (pin "136") (pinfunction "GND_136") (pintype "power_in"))
      (node (ref "U20") (pin "25") (pinfunction "GND_25") (pintype "power_in"))
      (node (ref "U20") (pin "3") (pinfunction "GND_3") (pintype "power_in"))
      (node (ref "U20") (pin "49") (pinfunction "GND_49") (pintype "power_in"))
      (node (ref "U20") (pin "54") (pinfunction "GND_54") (pintype "power_in"))
      (node (ref "U20") (pin "60") (pinfunction "IO_L13P_M1_2_60") (pintype "bidirectional"))
      (node (ref "U20") (pin "68") (pinfunction "GND_68") (pintype "power_in"))
      (node (ref "U20") (pin "73") (pinfunction "SUSPEND_73") (pintype "input"))
      (node (ref "U20") (pin "77") (pinfunction "GND_77") (pintype "power_in"))
      (node (ref "U20") (pin "91") (pinfunction "GND_91") (pintype "power_in"))
      (node (ref "U20") (pin "96") (pinfunction "GND_96") (pintype "power_in"))
      (node (ref "U21") (pin "8") (pinfunction "GND_8") (pintype "passive"))
      (node (ref "U22") (pin "8") (pinfunction "GND_8") (pintype "passive"))
      (node (ref "U23") (pin "8") (pinfunction "GND_8") (pintype "passive"))
      (node (ref "U24") (pin "4") (pinfunction "VSS_4") (pintype "power_in"))
    )
    (net (code "51") (name "/IN10") (class "Default")
      (node (ref "R186") (pin "1") (pinfunction "1_1") (pintype "passive"))
      (node (ref "U20") (pin "100") (pinfunction "IO_L33P_1_100") (pintype "bidirectional"))
    )
    (net (code "52") (name "/IN11") (class "Default")
      (node (ref "R191") (pin "1") (pinfunction "1_1") (pintype "passive"))
      (node (ref "U20") (pin "99") (pinfunction "IO_L33N_1_99") (pintype "bidirectional"))
    )
    (net (code "53") (name "/IN12") (class "Default")
      (node (ref "R196") (pin "1") (pinfunction "1_1") (pintype "passive"))
      (node (ref "U20") (pin "98") (pinfunction "IO_L34P_1_98") (pintype "bidirectional"))
    )
    (net (code "54") (name "/IN13") (class "Default")
      (node (ref "R201") (pin "1") (pinfunction "1_1") (pintype "passive"))
      (node (ref "U20") (pin "97") (pinfunction "IO_L34N_1_97") (pintype "bidirectional"))
    )
    (net (code "55") (name "/IN14") (class "Default")
      (node (ref "R206") (pin "1") (pinfunction "1_1") (pintype "passive"))
      (node (ref "U20") (pin "95") (pinfunction "IO_L40P_GCLK11_1_95") (pintype "bidirectional"))
    )
    (net (code "56") (name "/IN15") (class "Default")
      (node (ref "R211") (pin "1") (pinfunction "1_1") (pintype "passive"))
      (node (ref "U20") (pin "94") (pinfunction "IO_L40N_GCLK10_1_94") (pintype "bidirectional"))
    )
    (net (code "57") (name "/IN16") (class "Default")
      (node (ref "R216") (pin "1") (pinfunction "1_1") (pintype "passive"))
      (node (ref "U20") (pin "93") (pinfunction "IO_L41P_GCLK9_IRDY1_1_93") (pintype "bidirectional"))
    )
    (net (code "58") (name "/IN17") (class "Default")
      (node (ref "R221") (pin "1") (pinfunction "1_1") (pintype "passive"))
      (node (ref "U20") (pin "92") (pinfunction "IO_L41N_GCLK8_1_92") (pintype "bidirectional"))
    )
    (net (code "59") (name "/IN20") (class "Default")
      (node (ref "R226") (pin "1") (pinfunction "1_1") (pintype "passive"))
      (node (ref "U20") (pin "88") (pinfunction "IO_L42P_GCLK7_1_88") (pintype "bidirectional"))
    )
    (net (code "60") (name "/IN21") (class "Default")
      (node (ref "R231") (pin "1") (pinfunction "1_1") (pintype "passive"))
      (node (ref "U20") (pin "87") (pinfunction "IO_L42N_GCLK6_TRDY1_1_87") (pintype "bidirectional"))
    )
    (net (code "61") (name "/IN22") (class "Default")
      (node (ref "R236") (pin "1") (pinfunction "1_1") (pintype "passive"))
      (node (ref "U20") (pin "85") (pinfunction "IO_L43P_GCLK5_1_85") (pintype "bidirectional"))
    )
    (net (code "62") (name "/IN23") (class "Default")
      (node (ref "R241") (pin "1") (pinfunction "1_1") (pintype "passive"))
      (node (ref "U20") (pin "84") (pinfunction "IO_L43N_GCLK4_1_84") (pintype "bidirectional"))
    )
    (net (code "63") (name "/IN24") (class "Default")
      (node (ref "R246") (pin "1") (pinfunction "1_1") (pintype "passive"))
      (node (ref "U20") (pin "83") (pinfunction "IO_L45P_1_83") (pintype "bidirectional"))
    )
    (net (code "64") (name "/IN25") (class "Default")
      (node (ref "R251") (pin "1") (pinfunction "1_1") (pintype "passive"))
      (node (ref "U20") (pin "82") (pinfunction "IO_L45N_1_82") (pintype "bidirectional"))
    )
    (net (code "65") (name "/IN26") (class "Default")
      (node (ref "R257") (pin "1") (pinfunction "1_1") (pintype "passive"))
      (node (ref "U20") (pin "81") (pinfunction "IO_L46P_1_81") (pintype "bidirectional"))
    )
    (net (code "66") (name "/IN27") (class "Default")
      (node (ref "R262") (pin "1") (pinfunction "1_1") (pintype "passive"))
      (node (ref "U20") (pin "80") (pinfunction "IO_L46N_1_80") (pintype "bidirectional"))
    )
    (net (code "67") (name "/IN30") (class "Default")
      (node (ref "R266") (pin "1") (pinfunction "1_1") (pintype "passive"))
      (node (ref "U20") (pin "79") (pinfunction "IO_L47P_1_79") (pintype "bidirectional"))
    )
    (net (code "68") (name "/IN31") (class "Default")
      (node (ref "R270") (pin "1") (pinfunction "1_1") (pintype "passive"))
      (node (ref "U20") (pin "78") (pinfunction "IO_L47N_1_78") (pintype "bidirectional"))
    )
    (net (code "69") (name "/IN32") (class "Default")
      (node (ref "R274") (pin "1") (pinfunction "1_1") (pintype "passive"))
      (node (ref "U20") (pin "75") (pinfunction "IO_L74P_AWAKE_1_75") (pintype "bidirectional"))
    )
    (net (code "70") (name "/IN33") (class "Default")
      (node (ref "R277") (pin "1") (pinfunction "1_1") (pintype "passive"))
      (node (ref "U20") (pin "74") (pinfunction "IO_L74N_DOUT_BUSY_1_74") (pintype "bidirectional"))
    )
    (net (code "71") (name "/IN34") (class "Default")
      (node (ref "R163") (pin "1") (pinfunction "1_1") (pintype "passive"))
      (node (ref "U20") (pin "67") (pinfunction "IO_L2P_CMPCLK_2_67") (pintype "bidirectional"))
    )
    (net (code "72") (name "/IN35") (class "Default")
      (node (ref "R167") (pin "1") (pinfunction "1_1") (pintype "passive"))
      (node (ref "U20") (pin "66") (pinfunction "IO_L2N_CMPMOSI_2_66") (pintype "bidirectional"))
    )
    (net (code "73") (name "/IN36") (class "Default")
      (node (ref "R172") (pin "1") (pinfunction "1_1") (pintype "passive"))
      (node (ref "U20") (pin "62") (pinfunction "IO_L12P_D1_MISO2_2_62") (pintype "bidirectional"))
    )
    (net (code "74") (name "/IN37") (class "Default")
      (node (ref "R177") (pin "1") (pinfunction "1_1") (pintype "passive"))
      (node (ref "U20") (pin "61") (pinfunction "IO_L12N_D2_MISO3_2_61") (pintype "bidirectional"))
    )
    (net (code "75") (name "/IN40") (class "Default")
      (node (ref "R182") (pin "1") (pinfunction "1_1") (pintype "passive"))
      (node (ref "U20") (pin "55") (pinfunction "IO_L30N_GCLK0_USERCCLK_2_55") (pintype "bidirectional"))
    )
    (net (code "76") (name "/IN41") (class "Default")
      (node (ref "R187") (pin "1") (pinfunction "1_1") (pintype "passive"))
      (node (ref "U20") (pin "51") (pinfunction "IO_L31P_GCLK31_D14_2_51") (pintype "bidirectional"))
    )
    (net (code "77") (name "/IN42") (class "Default")
      (node (ref "R192") (pin "1") (pinfunction "1_1") (pintype "passive"))
      (node (ref "U20") (pin "50") (pinfunction "IO_L31N_GCLK30_D15_2_50") (pintype "bidirectional"))
    )
    (net (code "78") (name "/IN43") (class "Default")
      (node (ref "R197") (pin "1") (pinfunction "1_1") (pintype "passive"))
      (node (ref "U20") (pin "48") (pinfunction "IO_L48P_D7_2_48") (pintype "bidirectional"))
    )
    (net (code "79") (name "/IN44") (class "Default")
      (node (ref "R202") (pin "1") (pinfunction "1_1") (pintype "passive"))
      (node (ref "U20") (pin "47") (pinfunction "IO_L48N_RDWR_B_VREF_2_47") (pintype "bidirectional"))
    )
    (net (code "80") (name "/IN45") (class "Default")
      (node (ref "R207") (pin "1") (pinfunction "1_1") (pintype "passive"))
      (node (ref "U20") (pin "46") (pinfunction "IO_L49P_D3_2_46") (pintype "bidirectional"))
    )
    (net (code "81") (name "/IN46") (class "Default")
      (node (ref "R212") (pin "1") (pinfunction "1_1") (pintype "passive"))
      (node (ref "U20") (pin "45") (pinfunction "IO_L49N_D4_2_45") (pintype "bidirectional"))
    )
    (net (code "82") (name "/IN47") (class "Default")
      (node (ref "R217") (pin "1") (pinfunction "1_1") (pintype "passive"))
      (node (ref "U20") (pin "44") (pinfunction "IO_L62P_D5_2_44") (pintype "bidirectional"))
    )
    (net (code "83") (name "/IN50") (class "Default")
      (node (ref "R222") (pin "1") (pinfunction "1_1") (pintype "passive"))
      (node (ref "U20") (pin "43") (pinfunction "IO_L62N_D6_2_43") (pintype "bidirectional"))
    )
    (net (code "84") (name "/IN51") (class "Default")
      (node (ref "R227") (pin "1") (pinfunction "1_1") (pintype "passive"))
      (node (ref "U20") (pin "41") (pinfunction "IO_L64P_D8_2_41") (pintype "bidirectional"))
    )
    (net (code "85") (name "/IN52") (class "Default")
      (node (ref "R232") (pin "1") (pinfunction "1_1") (pintype "passive"))
      (node (ref "U20") (pin "40") (pinfunction "IO_L64N_D9_2_40") (pintype "bidirectional"))
    )
    (net (code "86") (name "/IN53") (class "Default")
      (node (ref "R237") (pin "1") (pinfunction "1_1") (pintype "passive"))
      (node (ref "U20") (pin "35") (pinfunction "IO_L1P_3_35") (pintype "bidirectional"))
    )
    (net (code "87") (name "/IN54") (class "Default")
      (node (ref "R242") (pin "1") (pinfunction "1_1") (pintype "passive"))
      (node (ref "U20") (pin "34") (pinfunction "IO_L1N_VREF_3_34") (pintype "bidirectional"))
    )
    (net (code "88") (name "/IN55") (class "Default")
      (node (ref "R247") (pin "1") (pinfunction "1_1") (pintype "passive"))
      (node (ref "U20") (pin "33") (pinfunction "IO_L2P_3_33") (pintype "bidirectional"))
    )
    (net (code "89") (name "/IN56") (class "Default")
      (node (ref "R252") (pin "1") (pinfunction "1_1") (pintype "passive"))
      (node (ref "U20") (pin "32") (pinfunction "IO_L2N_3_32") (pintype "bidirectional"))
    )
    (net (code "90") (name "/IN57") (class "Default")
      (node (ref "R158") (pin "1") (pinfunction "1_1") (pintype "passive"))
      (node (ref "U20") (pin "30") (pinfunction "IO_L36P_3_30") (pintype "bidirectional"))
    )
    (net (code "91") (name "/IN60") (class "Default")
      (node (ref "R159") (pin "1") (pinfunction "1_1") (pintype "passive"))
      (node (ref "U20") (pin "29") (pinfunction "IO_L36N_3_29") (pintype "bidirectional"))
    )
    (net (code "92") (name "/IN61") (class "Default")
      (node (ref "R160") (pin "1") (pinfunction "1_1") (pintype "passive"))
      (node (ref "U20") (pin "27") (pinfunction "IO_L37P_3_27") (pintype "bidirectional"))
    )
    (net (code "93") (name "/IN62") (class "Default")
      (node (ref "R161") (pin "1") (pinfunction "1_1") (pintype "passive"))
      (node (ref "U20") (pin "26") (pinfunction "IO_L37N_3_26") (pintype "bidirectional"))
    )
    (net (code "94") (name "/IN63") (class "Default")
      (node (ref "R162") (pin "1") (pinfunction "1_1") (pintype "passive"))
      (node (ref "U20") (pin "24") (pinfunction "IO_L41P_GCLK27_3_24") (pintype "bidirectional"))
    )
    (net (code "95") (name "/IN64") (class "Default")
      (node (ref "R164") (pin "1") (pinfunction "1_1") (pintype "passive"))
      (node (ref "U20") (pin "23") (pinfunction "IO_L41N_GCLK26_3_23") (pintype "bidirectional"))
    )
    (net (code "96") (name "/IN65") (class "Default")
      (node (ref "R168") (pin "1") (pinfunction "1_1") (pintype "passive"))
      (node (ref "U20") (pin "22") (pinfunction "IO_L42P_GCLK25_TRDY2_3_22") (pintype "bidirectional"))
    )
    (net (code "97") (name "/IN66") (class "Default")
      (node (ref "R173") (pin "1") (pinfunction "1_1") (pintype "passive"))
      (node (ref "U20") (pin "21") (pinfunction "IO_L42N_GCLK24_3_21") (pintype "bidirectional"))
    )
    (net (code "98") (name "/IN67") (class "Default")
      (node (ref "R178") (pin "1") (pinfunction "1_1") (pintype "passive"))
      (node (ref "U20") (pin "17") (pinfunction "IO_L43P_GCLK23_3_17") (pintype "bidirectional"))
    )
    (net (code "99") (name "/IN70") (class "Default")
      (node (ref "R183") (pin "1") (pinfunction "1_1") (pintype "passive"))
      (node (ref "U20") (pin "15") (pinfunction "IO_L44P_GCLK21_3_15") (pintype "bidirectional"))
    )
    (net (code "100") (name "/IN71") (class "Default")
      (node (ref "R188") (pin "1") (pinfunction "1_1") (pintype "passive"))
      (node (ref "U20") (pin "12") (pinfunction "IO_L49P_3_12") (pintype "bidirectional"))
    )
    (net (code "101") (name "/IN72") (class "Default")
      (node (ref "R193") (pin "1") (pinfunction "1_1") (pintype "passive"))
      (node (ref "U20") (pin "11") (pinfunction "IO_L49N_3_11") (pintype "bidirectional"))
    )
    (net (code "102") (name "/IN73") (class "Default")
      (node (ref "R198") (pin "1") (pinfunction "1_1") (pintype "passive"))
      (node (ref "U20") (pin "10") (pinfunction "IO_L50P_3_10") (pintype "bidirectional"))
    )
    (net (code "103") (name "/IN74") (class "Default")
      (node (ref "R203") (pin "1") (pinfunction "1_1") (pintype "passive"))
      (node (ref "U20") (pin "9") (pinfunction "IO_L50N_3_9") (pintype "bidirectional"))
    )
    (net (code "104") (name "/IN75") (class "Default")
      (node (ref "R208") (pin "1") (pinfunction "1_1") (pintype "passive"))
      (node (ref "U20") (pin "8") (pinfunction "IO_L51P_3_8") (pintype "bidirectional"))
    )
    (net (code "105") (name "/IN76") (class "Default")
      (node (ref "R213") (pin "1") (pinfunction "1_1") (pintype "passive"))
      (node (ref "U20") (pin "7") (pinfunction "IO_L51N_3_7") (pintype "bidirectional"))
    )
    (net (code "106") (name "/IN77") (class "Default")
      (node (ref "R218") (pin "1") (pinfunction "1_1") (pintype "passive"))
      (node (ref "U20") (pin "6") (pinfunction "IO_L52P_3_6") (pintype "bidirectional"))
    )
    (net (code "107") (name "/IN80") (class "Default")
      (node (ref "R223") (pin "1") (pinfunction "1_1") (pintype "passive"))
      (node (ref "U20") (pin "5") (pinfunction "IO_L52N_3_5") (pintype "bidirectional"))
    )
    (net (code "108") (name "/IN81") (class "Default")
      (node (ref "R228") (pin "1") (pinfunction "1_1") (pintype "passive"))
      (node (ref "U20") (pin "2") (pinfunction "IO_L83P_3_2") (pintype "bidirectional"))
    )
    (net (code "109") (name "/IN82") (class "Default")
      (node (ref "R233") (pin "1") (pinfunction "1_1") (pintype "passive"))
      (node (ref "U20") (pin "1") (pinfunction "IO_L83N_VREF_3_1") (pintype "bidirectional"))
    )
    (net (code "110") (name "/IN83") (class "Default")
      (node (ref "R154") (pin "1") (pinfunction "1_1") (pintype "passive"))
      (node (ref "U20") (pin "144") (pinfunction "IO_L1P_HSWAPEN_0_144") (pintype "bidirectional"))
    )
    (net (code "111") (name "/IN84") (class "Default")
      (node (ref "R243") (pin "1") (pinfunction "1_1") (pintype "passive"))
      (node (ref "U20") (pin "143") (pinfunction "IO_L1N_VREF_0_143") (pintype "bidirectional"))
    )
    (net (code "112") (name "/IN85") (class "Default")
      (node (ref "R248") (pin "1") (pinfunction "1_1") (pintype "passive"))
      (node (ref "U20") (pin "142") (pinfunction "IO_L2P_0_142") (pintype "bidirectional"))
    )
    (net (code "113") (name "/IN86") (class "Default")
      (node (ref "R253") (pin "1") (pinfunction "1_1") (pintype "passive"))
      (node (ref "U20") (pin "141") (pinfunction "IO_L2N_0_141") (pintype "bidirectional"))
    )
    (net (code "114") (name "/IN87") (class "Default")
      (node (ref "R258") (pin "1") (pinfunction "1_1") (pintype "passive"))
      (node (ref "U20") (pin "140") (pinfunction "IO_L3P_0_140") (pintype "bidirectional"))
    )
    (net (code "115") (name "/IN91") (class "Default")
      (node (ref "P18") (pin "1") (pinfunction "1_1") (pintype "passive"))
      (node (ref "U20") (pin "132") (pinfunction "IO_L35P_GCLK17_0_132") (pintype "bidirectional"))
    )
    (net (code "116") (name "/IN92") (class "Default")
      (node (ref "P18") (pin "2") (pinfunction "2_2") (pintype "passive"))
      (node (ref "U20") (pin "131") (pinfunction "IO_L35N_GCLK16_0_131") (pintype "bidirectional"))
    )
    (net (code "117") (name "/IN93") (class "Default")
      (node (ref "P18") (pin "3") (pinfunction "3_3") (pintype "passive"))
      (node (ref "U20") (pin "126") (pinfunction "IO_L36N_GCLK14_0_126") (pintype "bidirectional"))
    )
    (net (code "118") (name "/IN94") (class "Default")
      (node (ref "P18") (pin "4") (pinfunction "4_4") (pintype "passive"))
      (node (ref "R185") (pin "1") (pinfunction "1_1") (pintype "passive"))
      (node (ref "U20") (pin "124") (pinfunction "IO_L37P_GCLK13_0_124") (pintype "bidirectional"))
    )
    (net (code "119") (name "/INITB") (class "Default")
      (node (ref "R153") (pin "1") (pinfunction "1_1") (pintype "passive"))
      (node (ref "U20") (pin "39") (pinfunction "IO_L65P_INIT_B_2_39") (pintype "bidirectional"))
    )
    (net (code "120") (name "/M0") (class "Default")
      (node (ref "R155") (pin "1") (pinfunction "1_1") (pintype "passive"))
      (node (ref "U20") (pin "69") (pinfunction "IO_L1N_M0_CMPMISO_2_69") (pintype "bidirectional"))
    )
    (net (code "121") (name "/PROGB") (class "Default")
      (node (ref "P22") (pin "5") (pinfunction "5_5") (pintype "passive"))
      (node (ref "R310") (pin "1") (pinfunction "1_1") (pintype "passive"))
      (node (ref "U20") (pin "37") (pinfunction "PROGRAM_B_2_37") (pintype "input"))
    )
    (net (code "122") (name "/PSAVE1") (class "Default")
      (node (ref "R239") (pin "1") (pinfunction "1_1") (pintype "passive"))
      (node (ref "R293") (pin "1") (pinfunction "1_1") (pintype "passive"))
      (node (ref "U21") (pin "5") (pinfunction "QF_5") (pintype "passive"))
    )
    (net (code "123") (name "/PSAVE2") (class "Default")
      (node (ref "R244") (pin "1") (pinfunction "1_1") (pintype "passive"))
      (node (ref "R295") (pin "1") (pinfunction "1_1") (pintype "passive"))
      (node (ref "U22") (pin "15") (pinfunction "QA_15") (pintype "passive"))
    )
    (net (code "124") (name "/PSAVE3") (class "Default")
      (node (ref "R249") (pin "1") (pinfunction "1_1") (pintype "passive"))
      (node (ref "R297") (pin "1") (pinfunction "1_1") (pintype "passive"))
      (node (ref "U23") (pin "4") (pinfunction "QE_4") (pintype "passive"))
    )
    (net (code "126") (name "/REG_EN") (class "Default")
      (node (ref "R215") (pin "1") (pinfunction "1_1") (pintype "passive"))
      (node (ref "U20") (pin "134") (pinfunction "IO_L34P_GCLK19_0_134") (pintype "bidirectional"))
      (node (ref "U21") (pin "13") (pinfunction "~{ENOUT}_13") (pintype "passive"))
      (node (ref "U22") (pin "13") (pinfunction "~{ENOUT}_13") (pintype "passive"))
      (node (ref "U23") (pin "13") (pinfunction "~{ENOUT}_13") (pintype "passive"))
    )
    (net (code "127") (name "/REG_IN") (class "Default")
      (node (ref "R205") (pin "1") (pinfunction "1_1") (pintype "passive"))
      (node (ref "U20") (pin "133") (pinfunction "IO_L34N_GCLK18_0_133") (pintype "bidirectional"))
      (node (ref "U21") (pin "14") (pinfunction "A_14") (pintype "passive"))
    )
    (net (code "128") (name "/REG_LCLK") (class "Default")
      (node (ref "R225") (pin "1") (pinfunction "1_1") (pintype "passive"))
      (node (ref "U20") (pin "137") (pinfunction "IO_L4N_0_137") (pintype "bidirectional"))
      (node (ref "U21") (pin "12") (pinfunction "LCLK_12") (pintype "passive"))
      (node (ref "U22") (pin "12") (pinfunction "LCLK_12") (pintype "passive"))
      (node (ref "U23") (pin "12") (pinfunction "LCLK_12") (pintype "passive"))
    )
    (net (code "129") (name "/REG_OUT1") (class "Default")
      (node (ref "U21") (pin "9") (pinfunction "SQH_9") (pintype "passive"))
      (node (ref "U22") (pin "14") (pinfunction "A_14") (pintype "passive"))
    )
    (net (code "130") (name "/REG_OUT2") (class "Default")
      (node (ref "U22") (pin "9") (pinfunction "SQH_9") (pintype "passive"))
      (node (ref "U23") (pin "14") (pinfunction "A_14") (pintype "passive"))
    )
    (net (code "131") (name "/REG_RESET") (class "Default")
      (node (ref "R210") (pin "1") (pinfunction "1_1") (pintype "passive"))
      (node (ref "U20") (pin "139") (pinfunction "IO_L3N_0_139") (pintype "bidirectional"))
      (node (ref "U21") (pin "10") (pinfunction "~{RESET}_10") (pintype "passive"))
      (node (ref "U22") (pin "10") (pinfunction "~{RESET}_10") (pintype "passive"))
      (node (ref "U23") (pin "10") (pinfunction "~{RESET}_10") (pintype "passive"))
    )
    (net (code "132") (name "/REG_SCLK") (class "Default")
      (node (ref "R220") (pin "1") (pinfunction "1_1") (pintype "passive"))
      (node (ref "U20") (pin "138") (pinfunction "IO_L4P_0_138") (pintype "bidirectional"))
      (node (ref "U21") (pin "11") (pinfunction "SCLK_11") (pintype "passive"))
      (node (ref "U22") (pin "11") (pinfunction "SCLK_11") (pintype "passive"))
      (node (ref "U23") (pin "11") (pinfunction "SCLK_11") (pintype "passive"))
    )
    (net (code "133") (name "/SCS") (class "Default")
      (node (ref "P22") (pin "4") (pinfunction "4_4") (pintype "passive"))
      (node (ref "R302") (pin "2") (pinfunction "2_2") (pintype "passive"))
      (node (ref "R303") (pin "2") (pinfunction "2_2") (pintype "passive"))
      (node (ref "U20") (pin "38") (pinfunction "IO_L65N_CSO_B_2_38") (pintype "bidirectional"))
    )
    (net (code "134") (name "/SDO") (class "Default")
      (node (ref "P22") (pin "3") (pinfunction "3_3") (pintype "passive"))
      (node (ref "R301") (pin "2") (pinfunction "2_2") (pintype "passive"))
      (node (ref "R308") (pin "1") (pinfunction "1_1") (pintype "passive"))
      (node (ref "U20") (pin "64") (pinfunction "IO_L3N_MOSI_CSI_B_MISO0_2_64") (pintype "bidirectional"))
    )
    (net (code "135") (name "/SPI_CLK") (class "Default")
      (node (ref "R200") (pin "1") (pinfunction "1_1") (pintype "passive"))
      (node (ref "U20") (pin "59") (pinfunction "IO_L13N_D10_2_59") (pintype "bidirectional"))
    )
    (net (code "136") (name "/SPI_CS1") (class "Default")
      (node (ref "R254") (pin "1") (pinfunction "1_1") (pintype "passive"))
      (node (ref "R255") (pin "1") (pinfunction "1_1") (pintype "passive"))
    )
    (net (code "137") (name "/SPI_CS1O") (class "Default")
      (node (ref "R254") (pin "2") (pinfunction "2_2") (pintype "passive"))
      (node (ref "U21") (pin "3") (pinfunction "QD_3") (pintype "passive"))
    )
    (net (code "138") (name "/SPI_CS2") (class "Default")
      (node (ref "R259") (pin "1") (pinfunction "1_1") (pintype "passive"))
      (node (ref "R260") (pin "1") (pinfunction "1_1") (pintype "passive"))
    )
    (net (code "139") (name "/SPI_CS2O") (class "Default")
      (node (ref "R259") (pin "2") (pinfunction "2_2") (pintype "passive"))
      (node (ref "U23") (pin "3") (pinfunction "QD_3") (pintype "passive"))
    )
    (net (code "140") (name "/SPI_CS3") (class "Default")
      (node (ref "R263") (pin "1") (pinfunction "1_1") (pintype "passive"))
      (node (ref "R264") (pin "1") (pinfunction "1_1") (pintype "passive"))
    )
    (net (code "141") (name "/SPI_CS3O") (class "Default")
      (node (ref "R263") (pin "2") (pinfunction "2_2") (pintype "passive"))
      (node (ref "U21") (pin "6") (pinfunction "QG_6") (pintype "passive"))
    )
    (net (code "142") (name "/SPI_CS4") (class "Default")
      (node (ref "R267") (pin "1") (pinfunction "1_1") (pintype "passive"))
      (node (ref "R268") (pin "1") (pinfunction "1_1") (pintype "passive"))
    )
    (net (code "143") (name "/SPI_CS4O") (class "Default")
      (node (ref "R267") (pin "2") (pinfunction "2_2") (pintype "passive"))
      (node (ref "U22") (pin "6") (pinfunction "QG_6") (pintype "passive"))
    )
    (net (code "144") (name "/SPI_CS5") (class "Default")
      (node (ref "R271") (pin "1") (pinfunction "1_1") (pintype "passive"))
      (node (ref "R272") (pin "1") (pinfunction "1_1") (pintype "passive"))
    )
    (net (code "145") (name "/SPI_CS5O") (class "Default")
      (node (ref "R271") (pin "2") (pinfunction "2_2") (pintype "passive"))
      (node (ref "U23") (pin "6") (pinfunction "QG_6") (pintype "passive"))
    )
    (net (code "146") (name "/SPI_CS6") (class "Default")
      (node (ref "R275") (pin "1") (pinfunction "1_1") (pintype "passive"))
      (node (ref "R276") (pin "1") (pinfunction "1_1") (pintype "passive"))
    )
    (net (code "147") (name "/SPI_CS6O") (class "Default")
      (node (ref "R275") (pin "2") (pinfunction "2_2") (pintype "passive"))
      (node (ref "U23") (pin "1") (pinfunction "QB_1") (pintype "passive"))
    )
    (net (code "149") (name "/SPI_DIN") (class "Default")
      (node (ref "R190") (pin "1") (pinfunction "1_1") (pintype "passive"))
      (node (ref "U20") (pin "58") (pinfunction "IO_L14P_D11_2_58") (pintype "bidirectional"))
    )
    (net (code "150") (name "/SPI_DOUT") (class "Default")
      (node (ref "R195") (pin "1") (pinfunction "1_1") (pintype "passive"))
      (node (ref "U20") (pin "57") (pinfunction "IO_L14N_D12_2_57") (pintype "bidirectional"))
    )
    (net (code "151") (name "/TCK") (class "Default")
      (node (ref "P21") (pin "4") (pinfunction "4_4") (pintype "passive"))
      (node (ref "U20") (pin "109") (pinfunction "TCK_109") (pintype "input"))
    )
    (net (code "152") (name "/TDI") (class "Default")
      (node (ref "P21") (pin "2") (pinfunction "2_2") (pintype "passive"))
      (node (ref "U20") (pin "110") (pinfunction "TDI_110") (pintype "input"))
    )
    (net (code "153") (name "/TDO") (class "Default")
      (node (ref "P21") (pin "1") (pinfunction "1_1") (pintype "passive"))
      (node (ref "U20") (pin "106") (pinfunction "TDO_106") (pintype "output"))
    )
    (net (code "154") (name "/TMS") (class "Default")
      (node (ref "P21") (pin "3") (pinfunction "3_3") (pintype "passive"))
      (node (ref "U20") (pin "107") (pinfunction "TMS_107") (pintype "input"))
    )
    (net (code "155") (name "Net-(LED9-Pad1)") (class "Default")
      (node (ref "LED9") (pin "1") (pinfunction "1_1") (pintype "passive"))
      (node (ref "R278") (pin "2") (pinfunction "2_2") (pintype "passive"))
    )
    (net (code "156") (name "Net-(LED10-Pad1)") (class "Default")
      (node (ref "LED10") (pin "1") (pinfunction "1_1") (pintype "passive"))
      (node (ref "R279") (pin "2") (pinfunction "2_2") (pintype "passive"))
    )
    (net (code "157") (name "Net-(LED11-Pad1)") (class "Default")
      (node (ref "LED11") (pin "1") (pinfunction "1_1") (pintype "passive"))
      (node (ref "R280") (pin "2") (pinfunction "2_2") (pintype "passive"))
    )
    (net (code "158") (name "Net-(LED12-Pad1)") (class "Default")
      (node (ref "LED12") (pin "1") (pinfunction "1_1") (pintype "passive"))
      (node (ref "R281") (pin "2") (pinfunction "2_2") (pintype "passive"))
    )
    (net (code "159") (name "Net-(LED13-Pad1)") (class "Default")
      (node (ref "LED13") (pin "1") (pinfunction "1_1") (pintype "passive"))
      (node (ref "R282") (pin "2") (pinfunction "2_2") (pintype "passive"))
    )
    (net (code "160") (name "Net-(LED14-Pad1)") (class "Default")
      (node (ref "LED14") (pin "1") (pinfunction "1_1") (pintype "passive"))
      (node (ref "R283") (pin "2") (pinfunction "2_2") (pintype "passive"))
    )
    (net (code "161") (name "Net-(LED15-Pad1)") (class "Default")
      (node (ref "LED15") (pin "1") (pinfunction "1_1") (pintype "passive"))
      (node (ref "R284") (pin "2") (pinfunction "2_2") (pintype "passive"))
    )
    (net (code "162") (name "Net-(LED16-Pad1)") (class "Default")
      (node (ref "LED16") (pin "1") (pinfunction "1_1") (pintype "passive"))
      (node (ref "R285") (pin "2") (pinfunction "2_2") (pintype "passive"))
    )
    (net (code "163") (name "Net-(LED17-Pad1)") (class "Default")
      (node (ref "LED17") (pin "1") (pinfunction "1_1") (pintype "passive"))
      (node (ref "R286") (pin "2") (pinfunction "2_2") (pintype "passive"))
    )
    (net (code "164") (name "Net-(LED18-Pad1)") (class "Default")
      (node (ref "LED18") (pin "1") (pinfunction "1_1") (pintype "passive"))
      (node (ref "R287") (pin "2") (pinfunction "2_2") (pintype "passive"))
    )
    (net (code "165") (name "Net-(LED19-Pad1)") (class "Default")
      (node (ref "LED19") (pin "1") (pinfunction "1_1") (pintype "passive"))
      (node (ref "R288") (pin "2") (pinfunction "2_2") (pintype "passive"))
    )
    (net (code "166") (name "Net-(LED20-Pad1)") (class "Default")
      (node (ref "LED20") (pin "1") (pinfunction "1_1") (pintype "passive"))
      (node (ref "R289") (pin "2") (pinfunction "2_2") (pintype "passive"))
    )
    (net (code "167") (name "Net-(LED21-Pad1)") (class "Default")
      (node (ref "LED21") (pin "1") (pinfunction "1_1") (pintype "passive"))
      (node (ref "R290") (pin "2") (pinfunction "2_2") (pintype "passive"))
    )
    (net (code "168") (name "Net-(LED22-Pad1)") (class "Default")
      (node (ref "LED22") (pin "1") (pinfunction "1_1") (pintype "passive"))
      (node (ref "R291") (pin "2") (pinfunction "2_2") (pintype "passive"))
    )
    (net (code "169") (name "Net-(LED23-Pad1)") (class "Default")
      (node (ref "LED23") (pin "1") (pinfunction "1_1") (pintype "passive"))
      (node (ref "R292") (pin "2") (pinfunction "2_2") (pintype "passive"))
    )
    (net (code "170") (name "Net-(LED24-Pad1)") (class "Default")
      (node (ref "LED24") (pin "1") (pinfunction "1_1") (pintype "passive"))
      (node (ref "R293") (pin "2") (pinfunction "2_2") (pintype "passive"))
    )
    (net (code "171") (name "Net-(LED25-Pad1)") (class "Default")
      (node (ref "LED25") (pin "1") (pinfunction "1_1") (pintype "passive"))
      (node (ref "R294") (pin "2") (pinfunction "2_2") (pintype "passive"))
    )
    (net (code "172") (name "Net-(LED26-Pad1)") (class "Default")
      (node (ref "LED26") (pin "1") (pinfunction "1_1") (pintype "passive"))
      (node (ref "R295") (pin "2") (pinfunction "2_2") (pintype "passive"))
    )
    (net (code "173") (name "Net-(LED27-Pad1)") (class "Default")
      (node (ref "LED27") (pin "1") (pinfunction "1_1") (pintype "passive"))
      (node (ref "R296") (pin "2") (pinfunction "2_2") (pintype "passive"))
    )
    (net (code "174") (name "Net-(LED28-Pad1)") (class "Default")
      (node (ref "LED28") (pin "1") (pinfunction "1_1") (pintype "passive"))
      (node (ref "R297") (pin "2") (pinfunction "2_2") (pintype "passive"))
    )
    (net (code "175") (name "Net-(LED29-Pad1)") (class "Default")
      (node (ref "LED29") (pin "1") (pinfunction "1_1") (pintype "passive"))
      (node (ref "R298") (pin "2") (pinfunction "2_2") (pintype "passive"))
    )
    (net (code "176") (name "Net-(LED30-Pad1)") (class "Default")
      (node (ref "LED30") (pin "1") (pinfunction "1_1") (pintype "passive"))
      (node (ref "R299") (pin "2") (pinfunction "2_2") (pintype "passive"))
    )
    (net (code "177") (name "Net-(LED31-Pad2)") (class "Default")
      (node (ref "LED31") (pin "2") (pinfunction "2_2") (pintype "passive"))
      (node (ref "R311") (pin "1") (pinfunction "1_1") (pintype "passive"))
    )
    (net (code "178") (name "Net-(U24-C)") (class "Default")
      (node (ref "R307") (pin "2") (pinfunction "2_2") (pintype "passive"))
      (node (ref "U24") (pin "6") (pinfunction "C_6") (pintype "input"))
    )
    (net (code "179") (name "Net-(U24-DQ0)") (class "Default")
      (node (ref "R308") (pin "2") (pinfunction "2_2") (pintype "passive"))
      (node (ref "U24") (pin "5") (pinfunction "DQ0_5") (pintype "input"))
    )
    (net (code "180") (name "Net-(U24-DQ1)") (class "Default")
      (node (ref "R309") (pin "2") (pinfunction "2_2") (pintype "passive"))
      (node (ref "U24") (pin "2") (pinfunction "DQ1_2") (pintype "tri_state"))
    )
    (net (code "181") (name "Net-(U24-HOLD#)") (class "Default")
      (node (ref "R306") (pin "2") (pinfunction "2_2") (pintype "passive"))
      (node (ref "U24") (pin "7") (pinfunction "HOLD#_7") (pintype "input"))
    )
    (net (code "182") (name "Net-(U24-S#)") (class "Default")
      (node (ref "R303") (pin "1") (pinfunction "1_1") (pintype "passive"))
      (node (ref "R304") (pin "2") (pinfunction "2_2") (pintype "passive"))
      (node (ref "U24") (pin "1") (pinfunction "S#_1") (pintype "input"))
    )
    (net (code "183") (name "Net-(U24-W#)") (class "Default")
      (node (ref "R305") (pin "2") (pinfunction "2_2") (pintype "passive"))
      (node (ref "U24") (pin "3") (pinfunction "W#_3") (pintype "input"))
    )
    (net (code "184") (name "unconnected-(U20A-IO_L36P_GCLK15_0-Pad127)") (class "Default")
      (node (ref "U20") (pin "127") (pinfunction "IO_L36P_GCLK15_0_127") (pintype "bidirectional+no_connect"))
    )
    (net (code "185") (name "unconnected-(U20E-CMPCS_B_2-Pad72)") (class "Default")
      (node (ref "U20") (pin "72") (pinfunction "CMPCS_B_2_72") (pintype "input+no_connect"))
    )
    (net (code "186") (name "unconnected-(U23-SQH-Pad9)") (class "Default")
      (node (ref "U23") (pin "9") (pinfunction "SQH_9") (pintype "passive+no_connect"))
    )
  )
)
